# EEZ_DIB_DCP405_r1B1.net
KiCad netlist of a schematic drawn in EAGLE
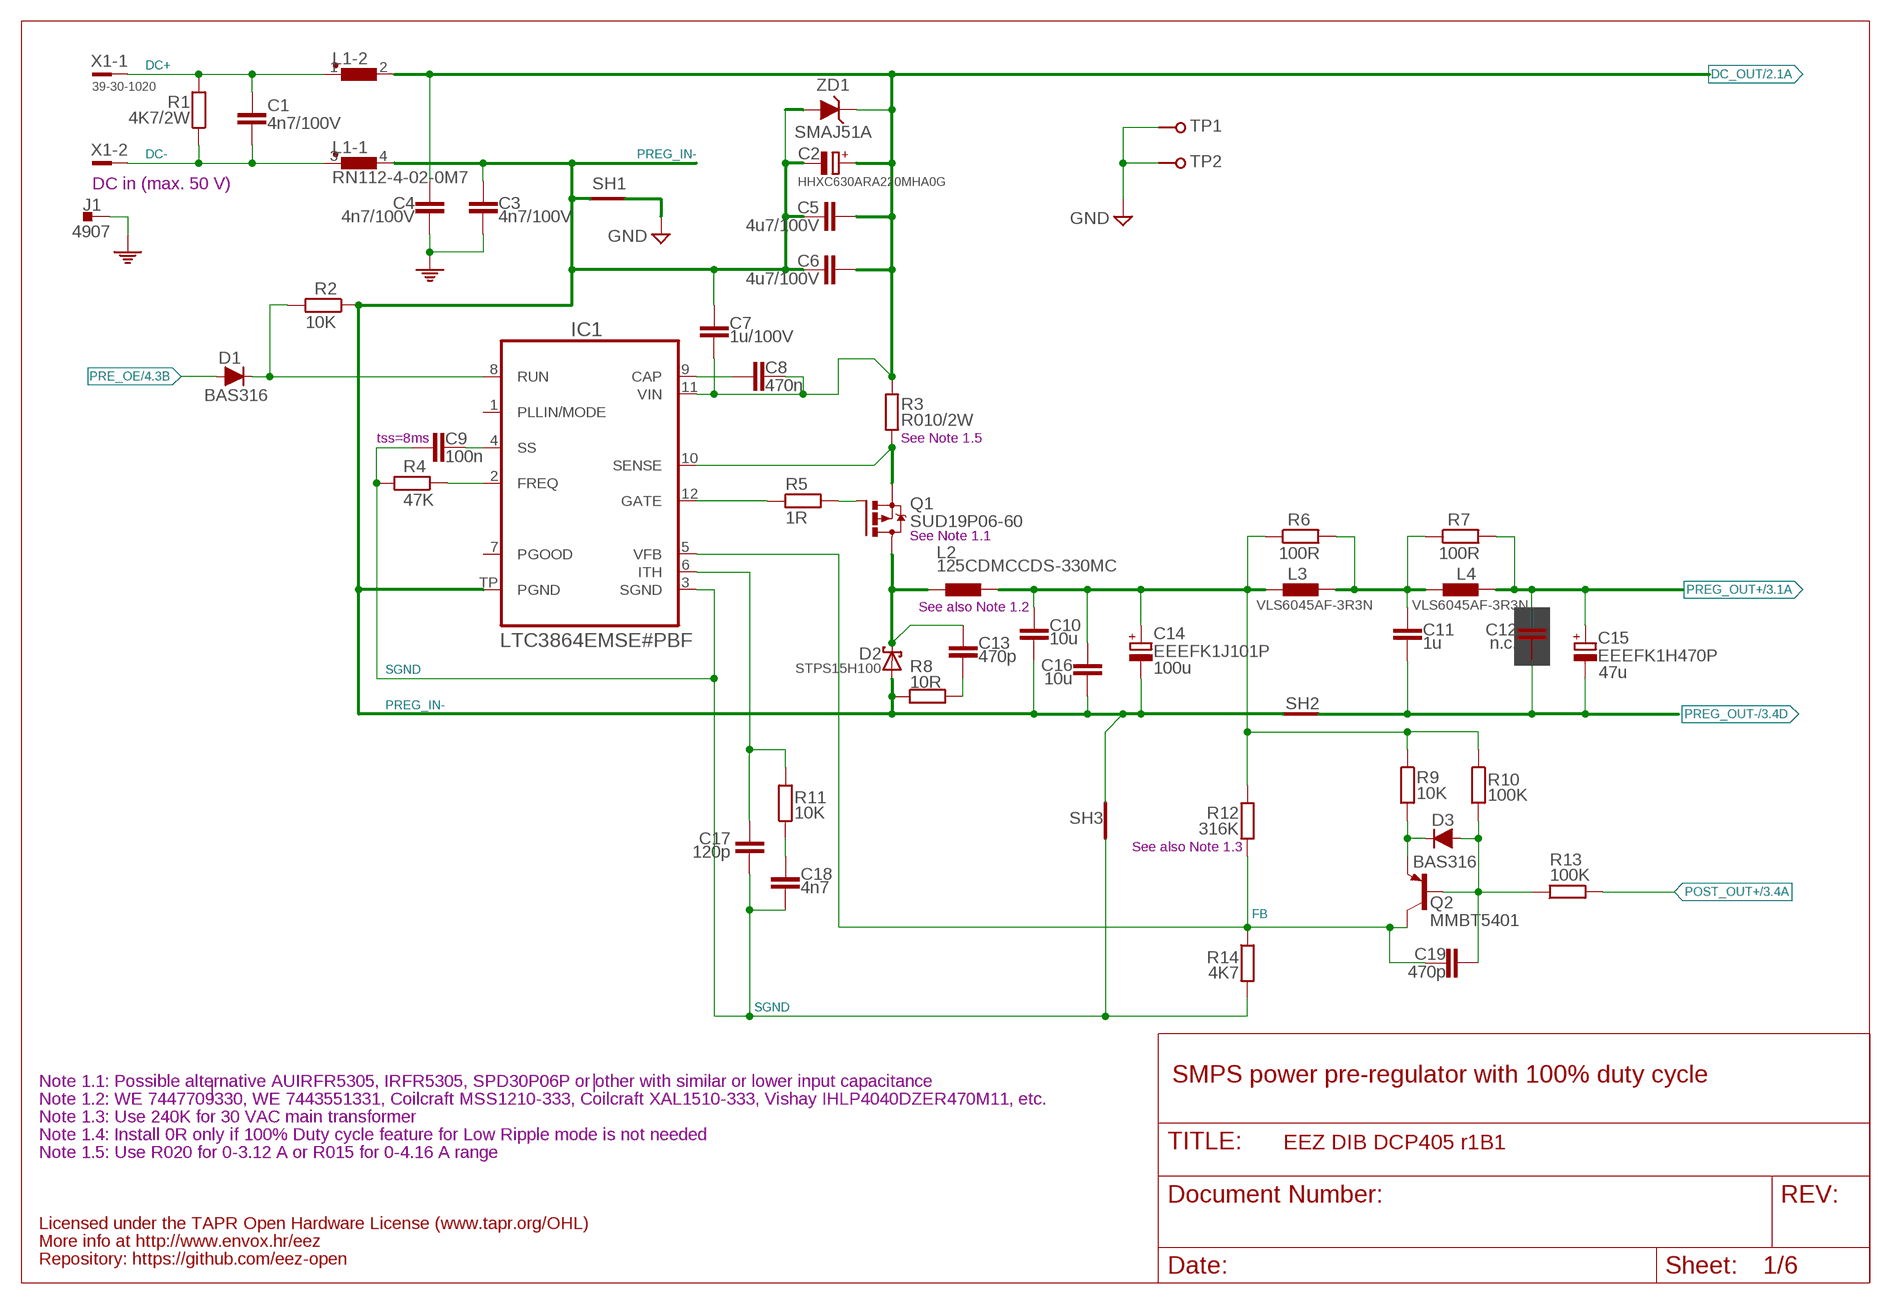
[diagram p0: schematic, sheet 1]
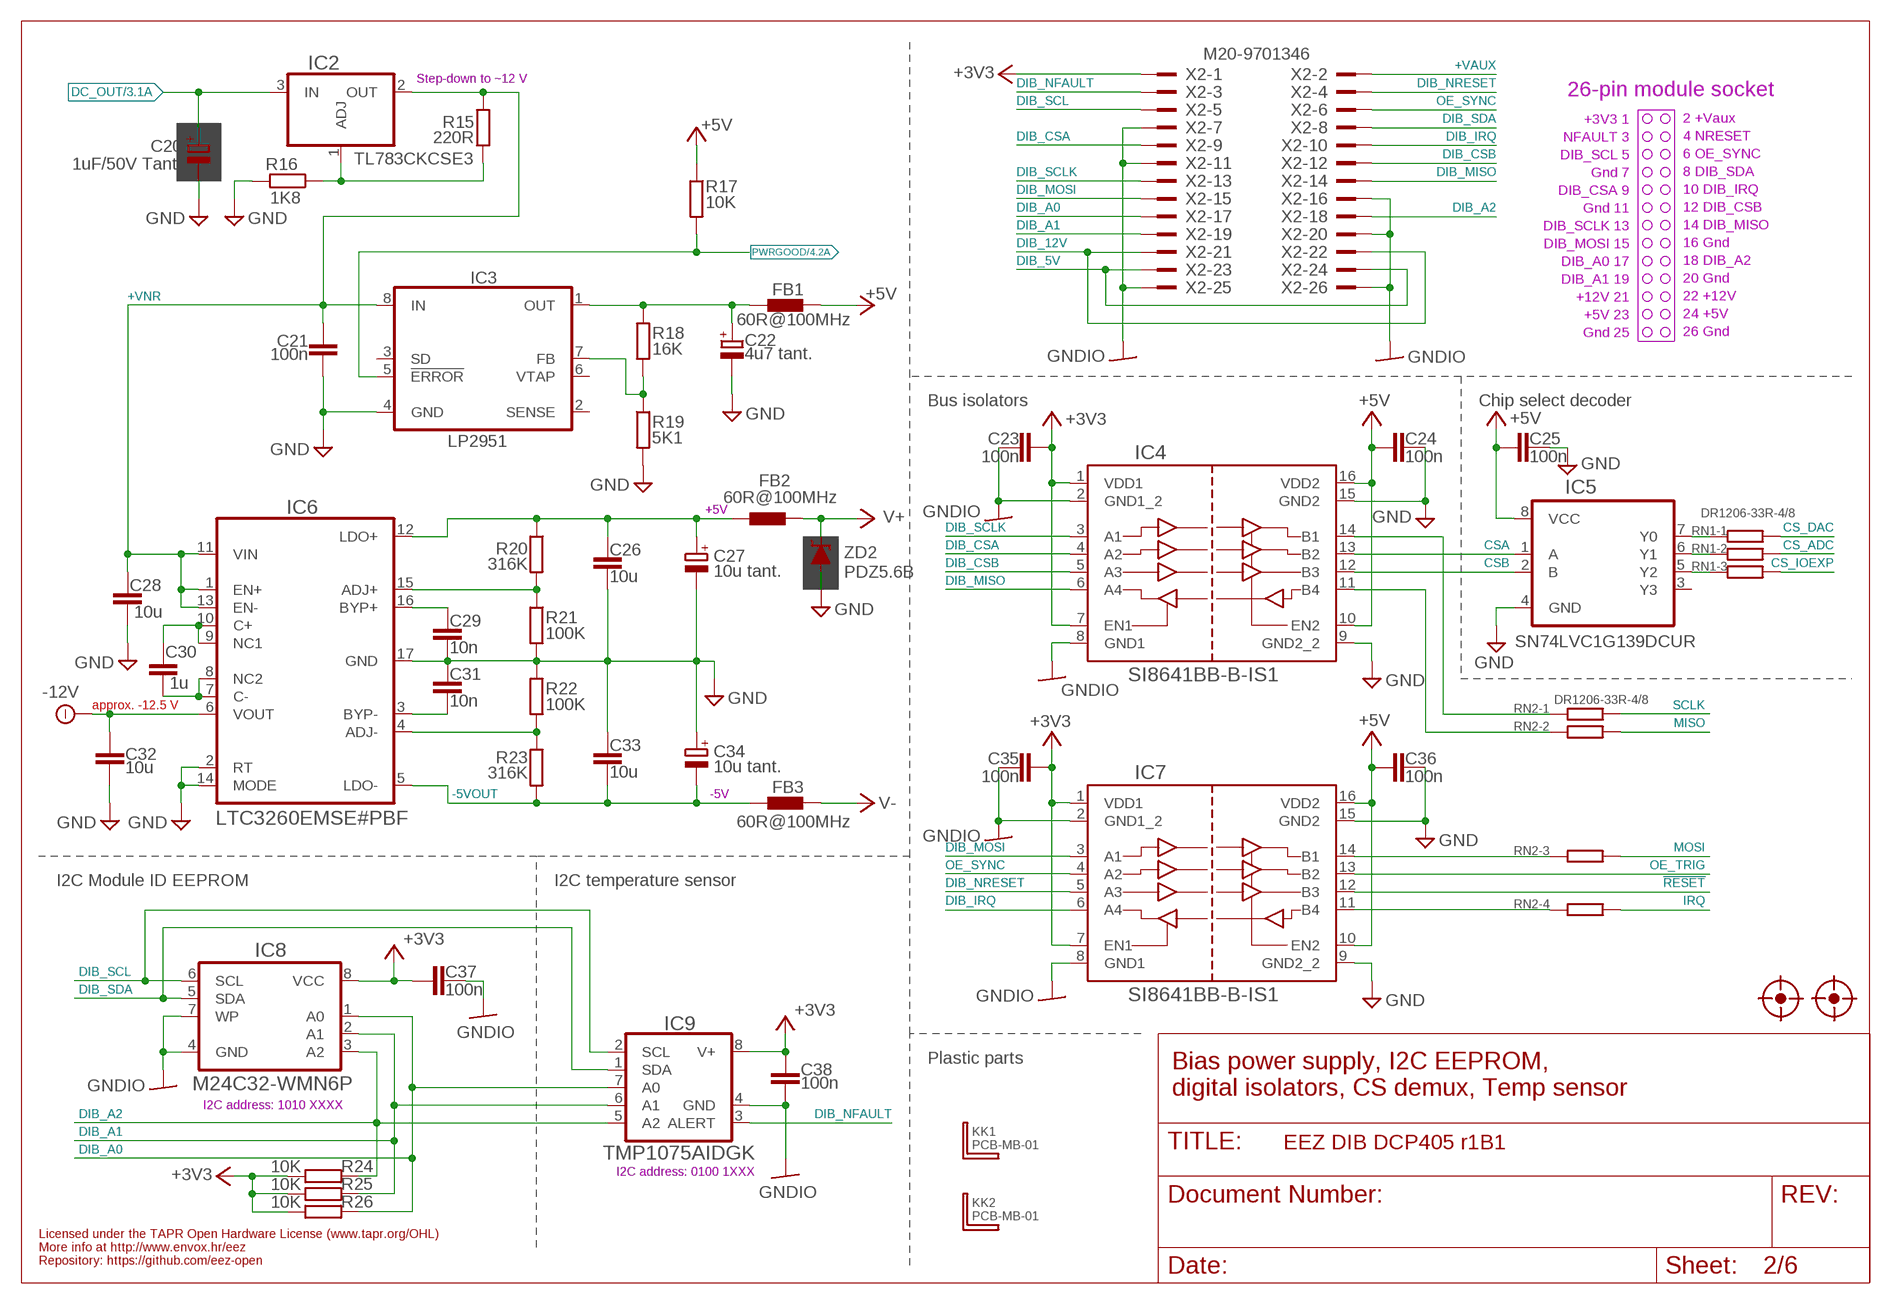
[diagram p1: schematic, sheet 2]
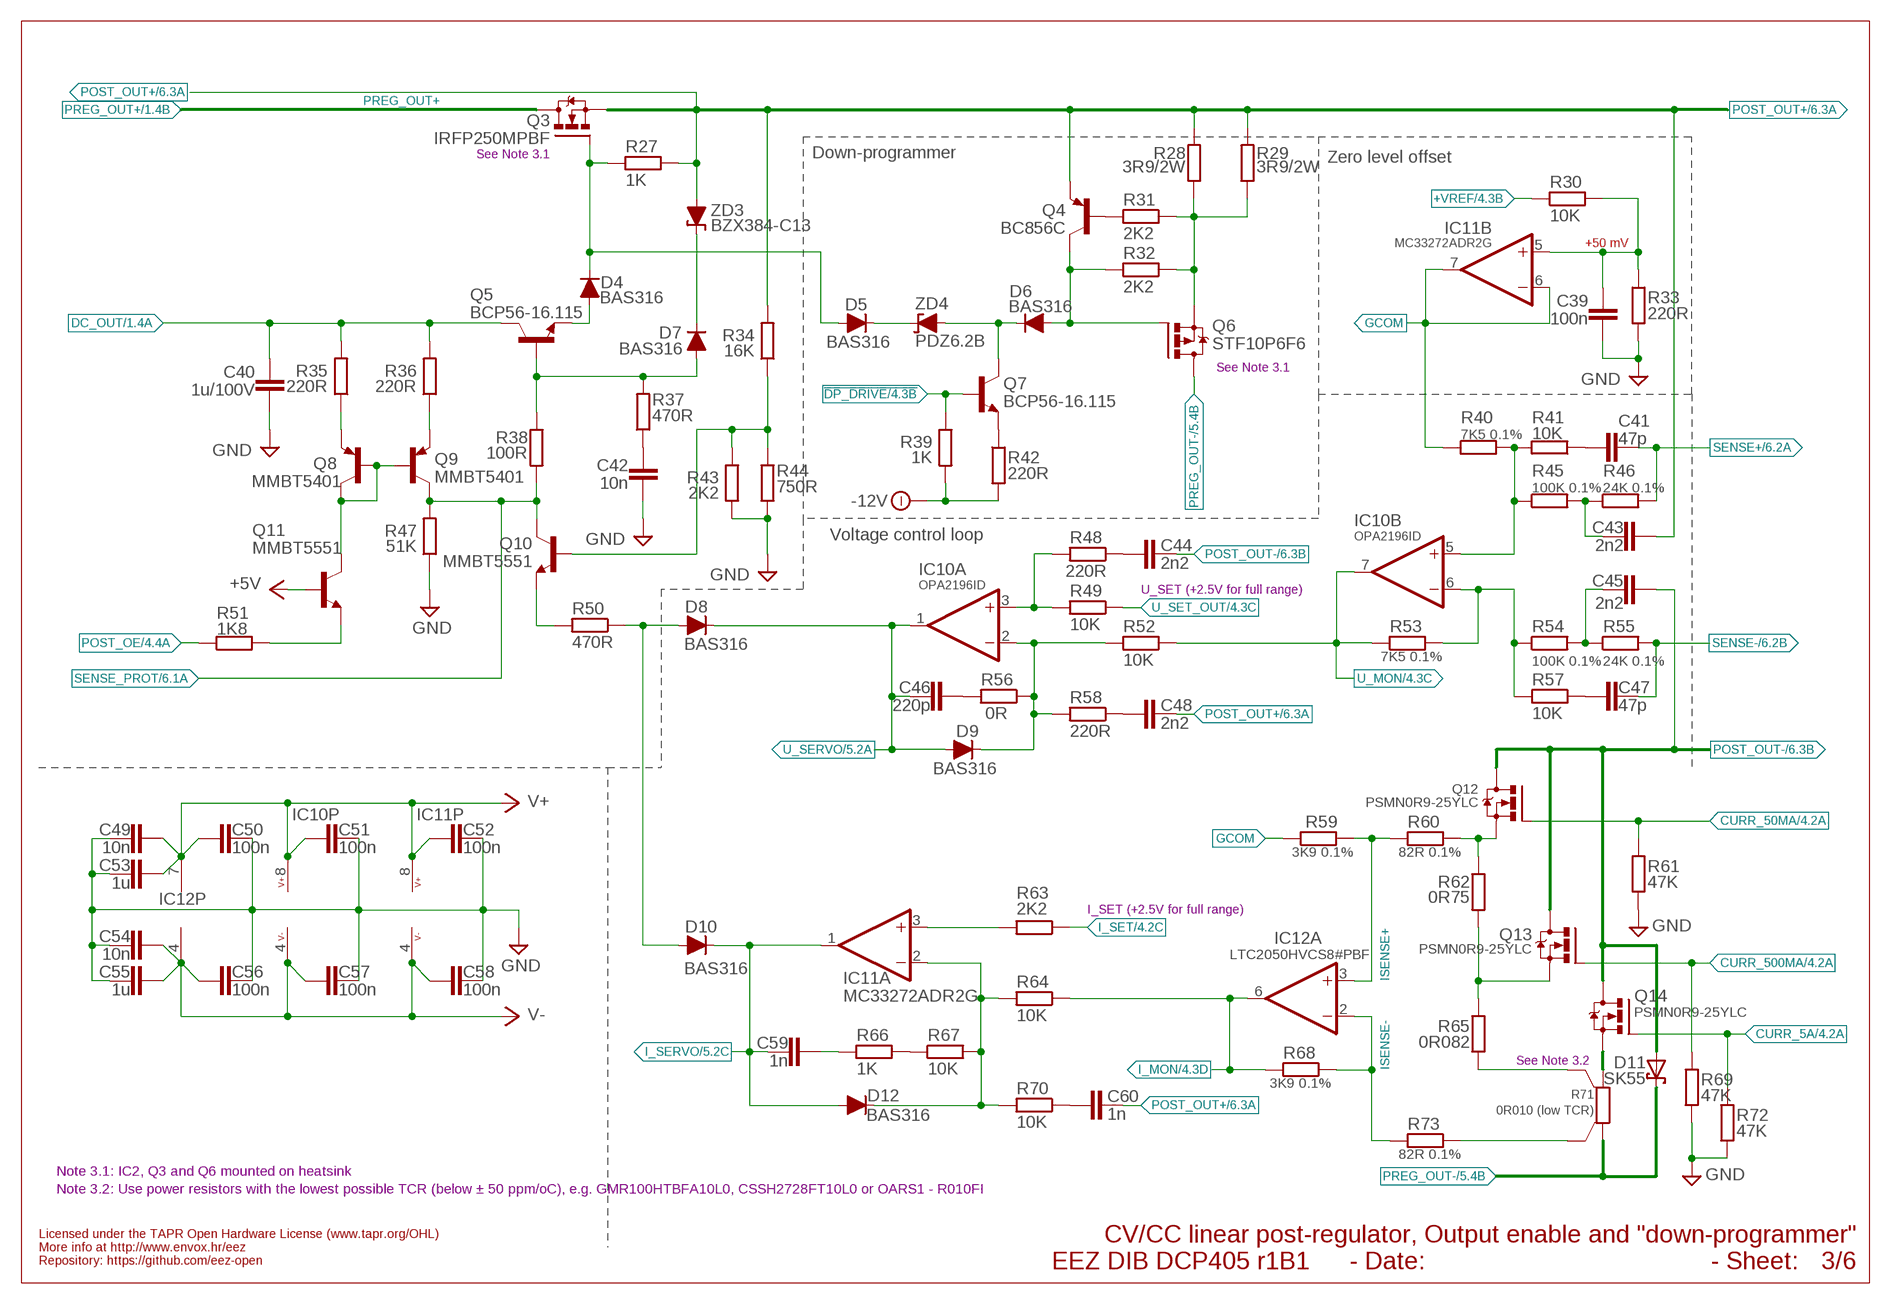
[diagram p2: schematic, sheet 3]
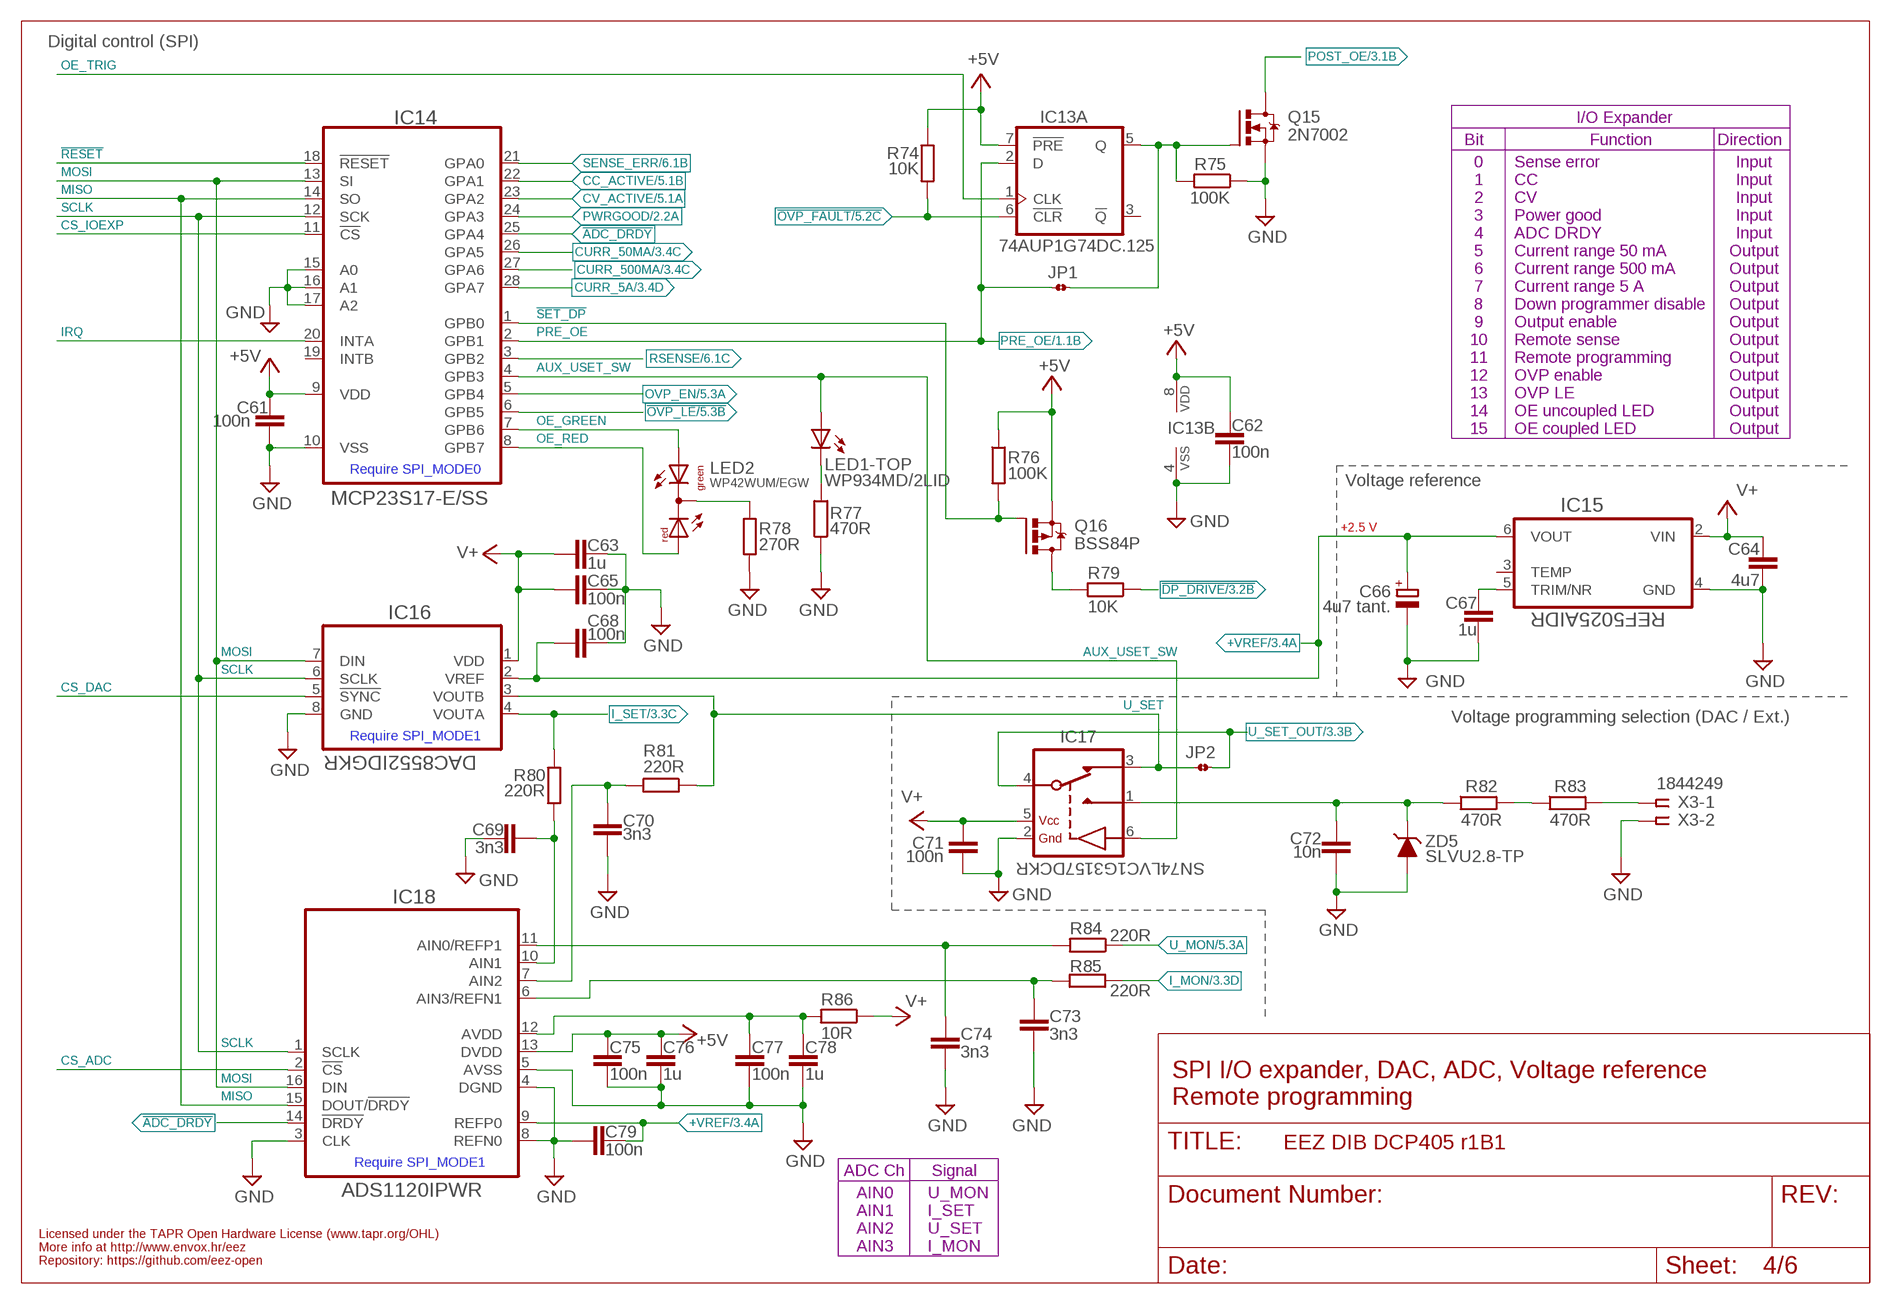
[diagram p3: schematic, sheet 4]
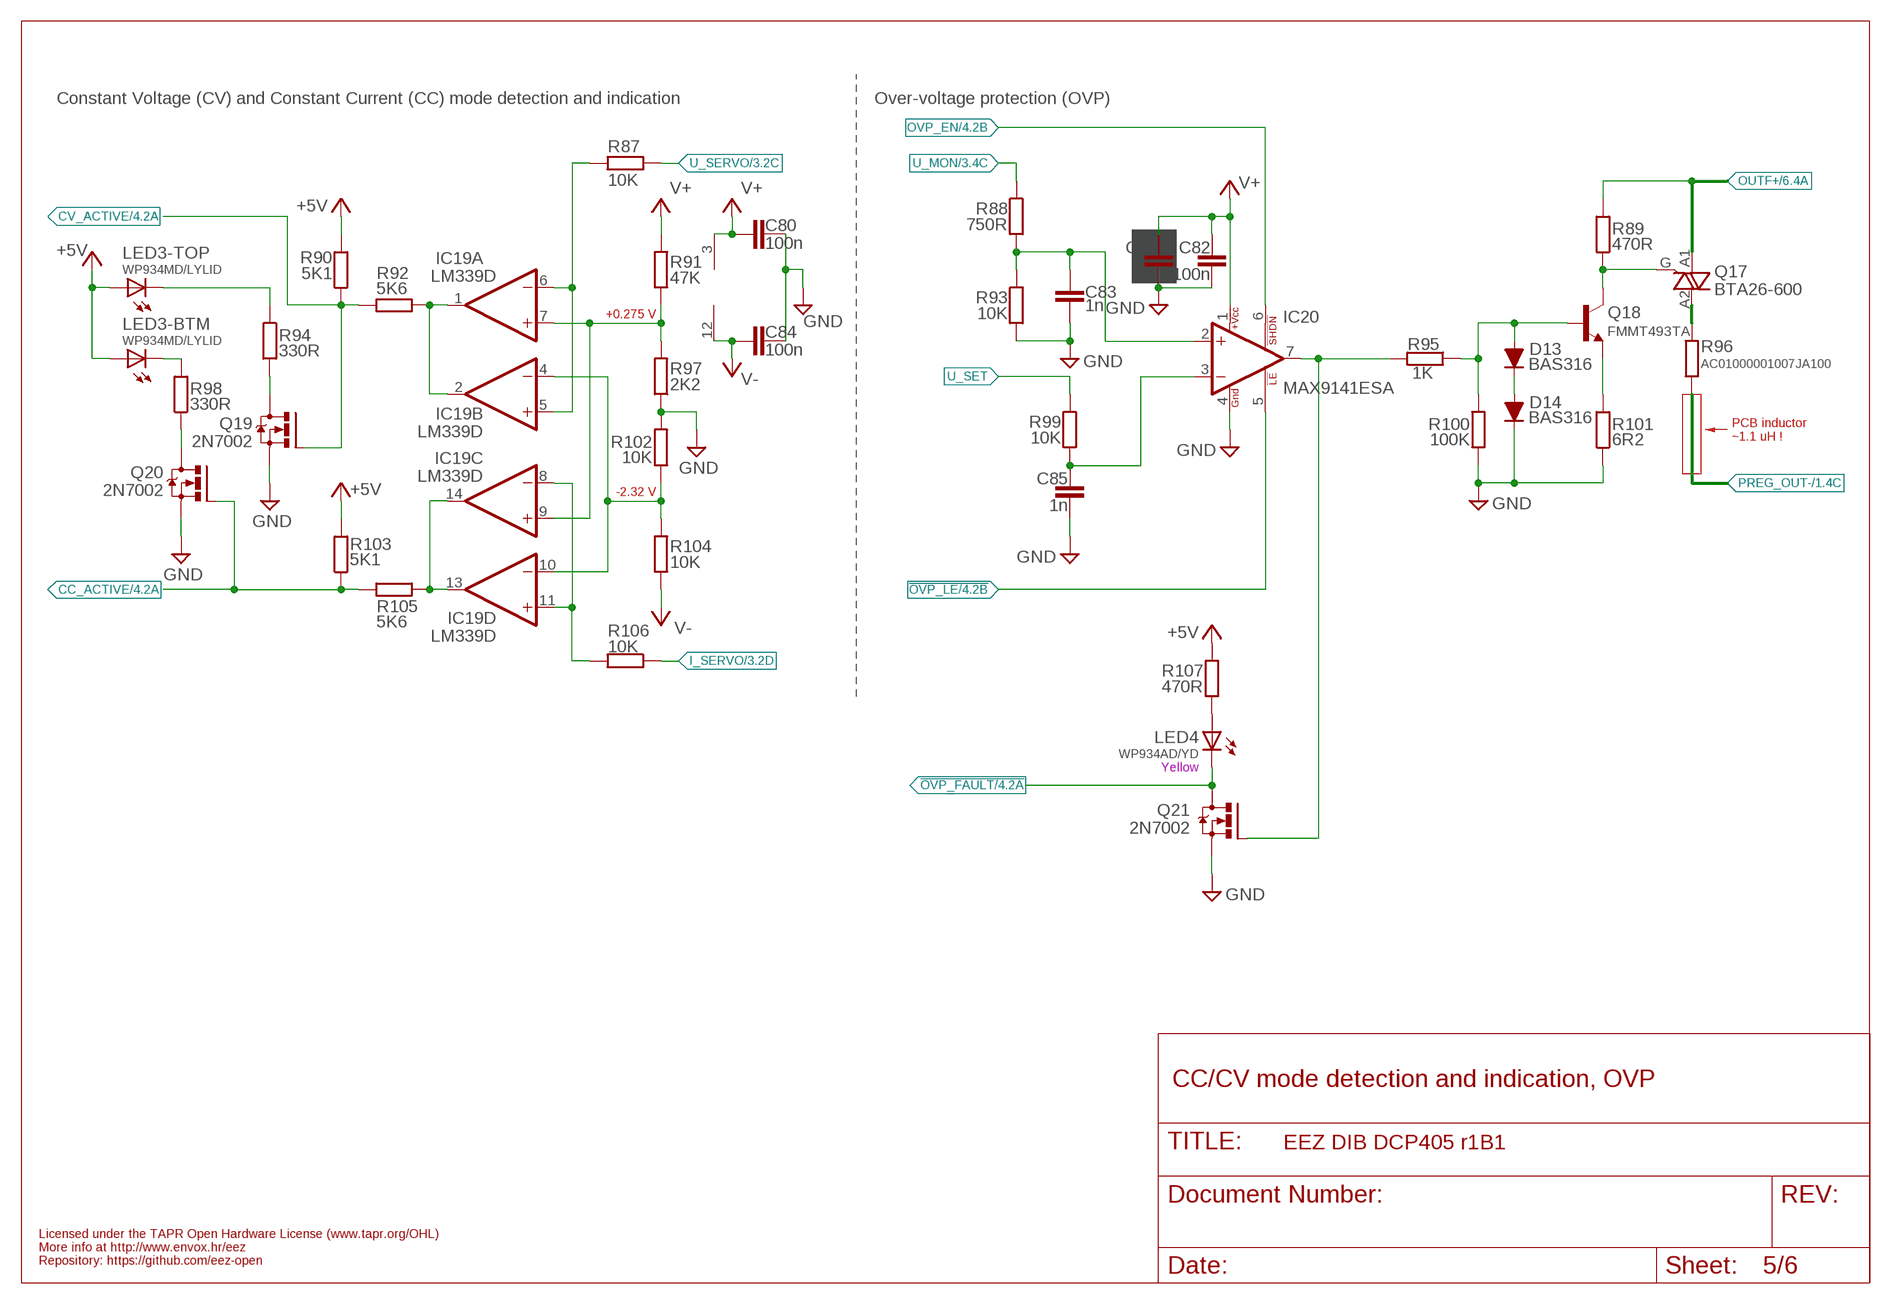
[diagram p4: schematic, sheet 5]
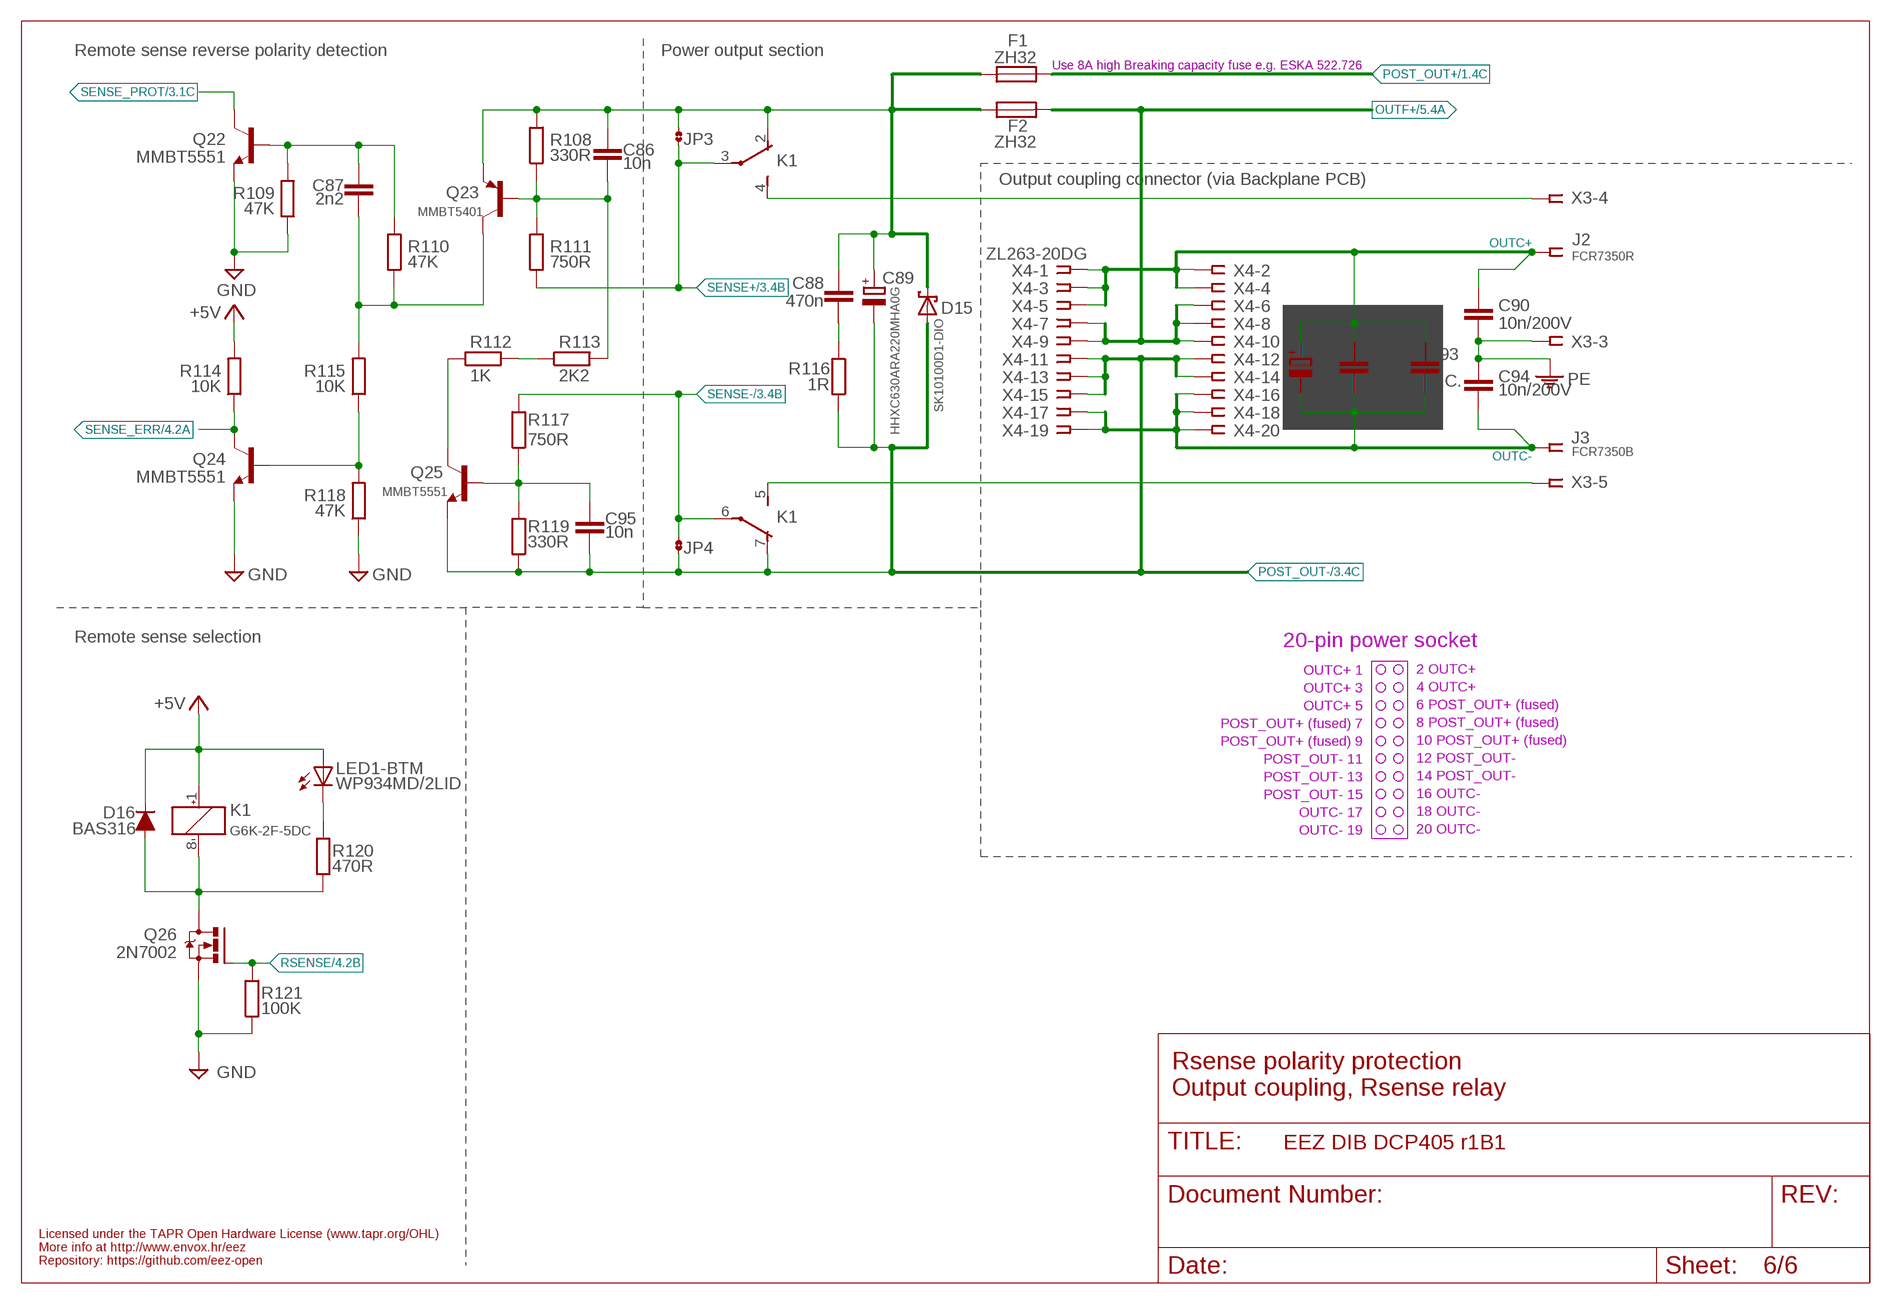
[diagram p5: schematic, sheet 6]

(export (version "E")
  (design (tool "Eeschema 10.0.6"))
  (components
    (comp (ref "C86")
      (value "10n")
      (footprint "eagle-import:C0805")
      (libsource (lib "eagle-import") (part "C-EUC0805"))
    )
    (comp (ref "C87")
      (value "2n2")
      (footprint "eagle-import:C0805")
      (libsource (lib "eagle-import") (part "C-EUC0805"))
    )
    (comp (ref "C88")
      (value "470n")
      (footprint "eagle-import:C1206")
      (libsource (lib "eagle-import") (part "C-EUC1206"))
    )
    (comp (ref "C89")
      (value "HHXC630ARA220MHA0G")
      (footprint "eagle-import:CAPAE830X1050N")
      (libsource (lib "eagle-import") (part "ECAPSMD8.3MM/HA0"))
    )
    (comp (ref "C90")
      (value "10n/200V")
      (footprint "eagle-import:C1206")
      (libsource (lib "eagle-import") (part "C-EUC1206"))
    )
    (comp (ref "C91")
      (value "N.C.")
      (footprint "eagle-import:ECAP2_5")
      (libsource (lib "eagle-import") (part "ECAP2G/5"))
    )
    (comp (ref "C92")
      (value "N.C.")
      (footprint "eagle-import:C0805")
      (libsource (lib "eagle-import") (part "C-EUC0805"))
    )
    (comp (ref "C93")
      (value "N.C.")
      (footprint "eagle-import:C0805")
      (libsource (lib "eagle-import") (part "C-EUC0805"))
    )
    (comp (ref "C94")
      (value "10n/200V")
      (footprint "eagle-import:C1206")
      (libsource (lib "eagle-import") (part "C-EUC1206"))
    )
    (comp (ref "C95")
      (value "10n")
      (footprint "eagle-import:C0805")
      (libsource (lib "eagle-import") (part "C-EUC0805"))
    )
    (comp (ref "D15")
      (value "SK10100D1-DIO")
      (footprint "eagle-import:TO252-L")
      (libsource (lib "eagle-import") (part "SCHOTTKY-DUAL_A_L"))
    )
    (comp (ref "D16")
      (value "BAS316")
      (footprint "eagle-import:SOD323-R")
      (libsource (lib "eagle-import") (part "DIODESOD323R"))
    )
    (comp (ref "F1")
      (value "ZH32")
      (footprint "eagle-import:ZH32")
      (libsource (lib "eagle-import") (part "ZH32"))
    )
    (comp (ref "F2")
      (value "ZH32")
      (footprint "eagle-import:ZH32")
      (libsource (lib "eagle-import") (part "ZH32"))
    )
    (comp (ref "J2")
      (value "FCR7350R")
      (footprint "eagle-import:S16N-PC")
      (libsource (lib "eagle-import") (part "BINDING_POSTCLIFF"))
    )
    (comp (ref "J3")
      (value "FCR7350B")
      (footprint "eagle-import:S16N-PC")
      (libsource (lib "eagle-import") (part "BINDING_POSTCLIFF"))
    )
    (comp (ref "JP3")
      (value "JP2-CUT")
      (footprint "eagle-import:JP2-CUT")
      (libsource (lib "eagle-import") (part "JP2-CUT"))
    )
    (comp (ref "JP4")
      (value "JP2-CUT")
      (footprint "eagle-import:JP2-CUT")
      (libsource (lib "eagle-import") (part "JP2-CUT"))
    )
    (comp (ref "K1")
      (value "G6K-2F-5DC")
      (footprint "eagle-import:G6K-2F")
      (fields
        (field (name "MF") "OMRON COMPONENTS USA")
        (field (name "MPN") "G6K-2F DC24")
        (field (name "MF_1") "OMRON COMPONENTS USA")
        (field (name "MPN_1") "G6K-2F DC24")
        (field (name "OC_FARNELL") "1690427")
        (field (name "OC_NEWARK") "36K7467")
      )
      (libsource (lib "eagle-import") (part "G6K-2F"))
    )
    (comp (ref "LED1")
      (value "WP934MD/2LID")
      (footprint "eagle-import:WP934MD")
      (libsource (lib "eagle-import") (part "WP934MD/2LID"))
    )
    (comp (ref "Q22")
      (value "MMBT5551")
      (footprint "eagle-import:SOT23-BEC")
      (libsource (lib "eagle-import") (part "-NPN-SOT23-BECMMBT5551LT1"))
    )
    (comp (ref "Q23")
      (value "MMBT5401")
      (footprint "eagle-import:SOT23-BEC")
      (libsource (lib "eagle-import") (part "-PNP-SOT23-BECBC857B"))
    )
    (comp (ref "Q24")
      (value "MMBT5551")
      (footprint "eagle-import:SOT23-BEC")
      (libsource (lib "eagle-import") (part "-NPN-SOT23-BECMMBT5551LT1"))
    )
    (comp (ref "Q25")
      (value "MMBT5551")
      (footprint "eagle-import:SOT23-BEC")
      (libsource (lib "eagle-import") (part "-NPN-SOT23-BECMMBT5551LT1"))
    )
    (comp (ref "Q26")
      (value "2N7002")
      (footprint "eagle-import:SOT103P240X110-3N")
      (fields
        (field (name "MPN") "2N7002-7-F")
        (field (name "MPN_1") "2N7002-7-F")
        (field (name "OC_FARNELL") "1713823")
        (field (name "OC_NEWARK") "25R5679")
        (field (name "PACKAGE") "SOT-23-3")
        (field (name "SUPPLIER") "DIODES INC.")
      )
      (libsource (lib "eagle-import") (part "2N7002"))
    )
    (comp (ref "R108")
      (value "330R")
      (footprint "eagle-import:R0805")
      (libsource (lib "eagle-import") (part "R-EU_R0805"))
    )
    (comp (ref "R109")
      (value "47K")
      (footprint "eagle-import:R0805")
      (libsource (lib "eagle-import") (part "R-EU_R0805"))
    )
    (comp (ref "R110")
      (value "47K")
      (footprint "eagle-import:R0805")
      (libsource (lib "eagle-import") (part "R-EU_R0805"))
    )
    (comp (ref "R111")
      (value "750R")
      (footprint "eagle-import:R0805")
      (libsource (lib "eagle-import") (part "R-EU_R0805"))
    )
    (comp (ref "R112")
      (value "1K")
      (footprint "eagle-import:R0805")
      (libsource (lib "eagle-import") (part "R-EU_R0805"))
    )
    (comp (ref "R113")
      (value "2K2")
      (footprint "eagle-import:R0805")
      (libsource (lib "eagle-import") (part "R-EU_R0805"))
    )
    (comp (ref "R114")
      (value "10K")
      (footprint "eagle-import:R0805")
      (libsource (lib "eagle-import") (part "R-EU_R0805"))
    )
    (comp (ref "R115")
      (value "10K")
      (footprint "eagle-import:R0805")
      (libsource (lib "eagle-import") (part "R-EU_R0805"))
    )
    (comp (ref "R116")
      (value "1R")
      (footprint "eagle-import:R0805")
      (libsource (lib "eagle-import") (part "R-EU_R0805"))
    )
    (comp (ref "R117")
      (value "750R")
      (footprint "eagle-import:R0805")
      (libsource (lib "eagle-import") (part "R-EU_R0805"))
    )
    (comp (ref "R118")
      (value "47K")
      (footprint "eagle-import:R0805")
      (libsource (lib "eagle-import") (part "R-EU_R0805"))
    )
    (comp (ref "R119")
      (value "330R")
      (footprint "eagle-import:R0805")
      (libsource (lib "eagle-import") (part "R-EU_R0805"))
    )
    (comp (ref "R120")
      (value "470R")
      (footprint "eagle-import:R0805")
      (libsource (lib "eagle-import") (part "R-EU_R0805"))
    )
    (comp (ref "R121")
      (value "100K")
      (footprint "eagle-import:R0805")
      (libsource (lib "eagle-import") (part "R-EU_R0805"))
    )
    (comp (ref "X3")
      (value "1844249")
      (footprint "eagle-import:MC1,5_5-G-3,5")
      (libsource (lib "eagle-import") (part "MC1,5/5-G-3,5"))
    )
    (comp (ref "X4")
      (value "ZL263-20DG")
      (footprint "eagle-import:SSW-110-02-T-D-RA")
      (libsource (lib "eagle-import") (part "SSW-110-02-T-D-RA"))
    )
    (comp (ref "C80")
      (value "100n")
      (footprint "eagle-import:C0603")
      (libsource (lib "eagle-import") (part "C-EUC0603"))
    )
    (comp (ref "C81")
      (value "1u")
      (footprint "eagle-import:C0805")
      (libsource (lib "eagle-import") (part "C-EUC0805"))
    )
    (comp (ref "C82")
      (value "100n")
      (footprint "eagle-import:C0603")
      (libsource (lib "eagle-import") (part "C-EUC0603"))
    )
    (comp (ref "C83")
      (value "1n")
      (footprint "eagle-import:C0805")
      (libsource (lib "eagle-import") (part "C-EUC0805"))
    )
    (comp (ref "C84")
      (value "100n")
      (footprint "eagle-import:C0603")
      (libsource (lib "eagle-import") (part "C-EUC0603"))
    )
    (comp (ref "C85")
      (value "1n")
      (footprint "eagle-import:C0805")
      (libsource (lib "eagle-import") (part "C-EUC0805"))
    )
    (comp (ref "D13")
      (value "BAS316")
      (footprint "eagle-import:SOD323-R")
      (libsource (lib "eagle-import") (part "DIODESOD323R"))
    )
    (comp (ref "D14")
      (value "BAS316")
      (footprint "eagle-import:SOD323-R")
      (libsource (lib "eagle-import") (part "DIODESOD323R"))
    )
    (comp (ref "IC19")
      (value "LM339D")
      (footprint "eagle-import:SOIC127P600X175-14N")
      (libsource (lib "eagle-import") (part "LM339SO14"))
    )
    (comp (ref "IC20")
      (value "MAX9141ESA")
      (footprint "eagle-import:SOIC127P600X173-8N")
      (libsource (lib "eagle-import") (part "MAX9141ESA"))
    )
    (comp (ref "LED3")
      (value "WP934MD/LYLID")
      (footprint "eagle-import:WP934MD")
      (libsource (lib "eagle-import") (part "WP934MD/LYLID"))
    )
    (comp (ref "LED4")
      (value "WP934AD/YD")
      (footprint "eagle-import:WP934AD")
      (libsource (lib "eagle-import") (part "WP934AD/YD"))
    )
    (comp (ref "Q17")
      (value "BTA26-600")
      (footprint "eagle-import:TOP3_TRIAC_NOHOLE")
      (libsource (lib "eagle-import") (part "BTA41-2"))
    )
    (comp (ref "Q18")
      (value "FMMT493TA")
      (footprint "eagle-import:SOT23-BEC")
      (libsource (lib "eagle-import") (part "-NPN-SOT23-BECMMBT5551LT1"))
    )
    (comp (ref "Q19")
      (value "2N7002")
      (footprint "eagle-import:SOT103P240X110-3N")
      (fields (field (name "MPN") "2N7002-7-F"))
      (libsource (lib "eagle-import") (part "2N7002"))
    )
    (comp (ref "Q20")
      (value "2N7002")
      (footprint "eagle-import:SOT103P240X110-3N")
      (fields (field (name "MPN") "2N7002-7-F"))
      (libsource (lib "eagle-import") (part "2N7002"))
    )
    (comp (ref "Q21")
      (value "2N7002")
      (footprint "eagle-import:SOT103P240X110-3N")
      (fields
        (field (name "MPN") "2N7002-7-F")
        (field (name "MPN_1") "2N7002-7-F")
        (field (name "OC_FARNELL") "1713823")
        (field (name "OC_NEWARK") "25R5679")
        (field (name "PACKAGE") "SOT-23-3")
        (field (name "SUPPLIER") "DIODES INC.")
      )
      (libsource (lib "eagle-import") (part "2N7002"))
    )
    (comp (ref "R87")
      (value "10K")
      (footprint "eagle-import:R0805")
      (libsource (lib "eagle-import") (part "R-EU_R0805"))
    )
    (comp (ref "R88")
      (value "750R")
      (footprint "eagle-import:R0805")
      (libsource (lib "eagle-import") (part "R-EU_R0805"))
    )
    (comp (ref "R89")
      (value "470R")
      (footprint "eagle-import:R0805")
      (libsource (lib "eagle-import") (part "R-EU_R0805"))
    )
    (comp (ref "R90")
      (value "5K1")
      (footprint "eagle-import:R0805")
      (libsource (lib "eagle-import") (part "R-EU_R0805"))
    )
    (comp (ref "R91")
      (value "47K")
      (footprint "eagle-import:R0805")
      (libsource (lib "eagle-import") (part "R-EU_R0805"))
    )
    (comp (ref "R92")
      (value "5K6")
      (footprint "eagle-import:R0805")
      (libsource (lib "eagle-import") (part "R-EU_R0805"))
    )
    (comp (ref "R93")
      (value "10K")
      (footprint "eagle-import:R0805")
      (libsource (lib "eagle-import") (part "R-EU_R0805"))
    )
    (comp (ref "R94")
      (value "330R")
      (footprint "eagle-import:R0805")
      (libsource (lib "eagle-import") (part "R-EU_R0805"))
    )
    (comp (ref "R95")
      (value "1K")
      (footprint "eagle-import:R0805")
      (libsource (lib "eagle-import") (part "R-EU_R0805"))
    )
    (comp (ref "R96")
      (value "AC01000001007JA100")
      (footprint "eagle-import:0411_15")
      (libsource (lib "eagle-import") (part "R-EU_0411/15"))
    )
    (comp (ref "R97")
      (value "2K2")
      (footprint "eagle-import:R0805")
      (libsource (lib "eagle-import") (part "R-EU_R0805"))
    )
    (comp (ref "R98")
      (value "330R")
      (footprint "eagle-import:R0805")
      (libsource (lib "eagle-import") (part "R-EU_R0805"))
    )
    (comp (ref "R99")
      (value "10K")
      (footprint "eagle-import:R0805")
      (libsource (lib "eagle-import") (part "R-EU_R0805"))
    )
    (comp (ref "R100")
      (value "100K")
      (footprint "eagle-import:R0805")
      (libsource (lib "eagle-import") (part "R-EU_R0805"))
    )
    (comp (ref "R101")
      (value "6R2")
      (footprint "eagle-import:R0805")
      (libsource (lib "eagle-import") (part "R-EU_R0805"))
    )
    (comp (ref "R102")
      (value "10K")
      (footprint "eagle-import:R0805")
      (libsource (lib "eagle-import") (part "R-EU_R0805"))
    )
    (comp (ref "R103")
      (value "5K1")
      (footprint "eagle-import:R0805")
      (libsource (lib "eagle-import") (part "R-EU_R0805"))
    )
    (comp (ref "R104")
      (value "10K")
      (footprint "eagle-import:R0805")
      (libsource (lib "eagle-import") (part "R-EU_R0805"))
    )
    (comp (ref "R105")
      (value "5K6")
      (footprint "eagle-import:R0805")
      (libsource (lib "eagle-import") (part "R-EU_R0805"))
    )
    (comp (ref "R106")
      (value "10K")
      (footprint "eagle-import:R0805")
      (libsource (lib "eagle-import") (part "R-EU_R0805"))
    )
    (comp (ref "R107")
      (value "470R")
      (footprint "eagle-import:R0805")
      (libsource (lib "eagle-import") (part "R-EU_R0805"))
    )
    (comp (ref "C61")
      (value "100n")
      (footprint "eagle-import:C0603")
      (libsource (lib "eagle-import") (part "C-EUC0603"))
    )
    (comp (ref "C62")
      (value "100n")
      (footprint "eagle-import:C0603")
      (libsource (lib "eagle-import") (part "C-EUC0603"))
    )
    (comp (ref "C63")
      (value "1u")
      (footprint "eagle-import:C0805")
      (libsource (lib "eagle-import") (part "C-EUC0805"))
    )
    (comp (ref "C64")
      (value "4u7")
      (footprint "eagle-import:C1206")
      (libsource (lib "eagle-import") (part "C-EUC1206"))
    )
    (comp (ref "C65")
      (value "100n")
      (footprint "eagle-import:C0603")
      (libsource (lib "eagle-import") (part "C-EUC0603"))
    )
    (comp (ref "C66")
      (value "4u7 tant.")
      (footprint "eagle-import:EC1206")
      (libsource (lib "eagle-import") (part "ECAP1206"))
    )
    (comp (ref "C67")
      (value "1u")
      (footprint "eagle-import:C0805")
      (libsource (lib "eagle-import") (part "C-EUC0805"))
    )
    (comp (ref "C68")
      (value "100n")
      (footprint "eagle-import:C0603")
      (libsource (lib "eagle-import") (part "C-EUC0603"))
    )
    (comp (ref "C69")
      (value "3n3")
      (footprint "eagle-import:C0805")
      (libsource (lib "eagle-import") (part "C-EUC0805"))
    )
    (comp (ref "C70")
      (value "3n3")
      (footprint "eagle-import:C0805")
      (libsource (lib "eagle-import") (part "C-EUC0805"))
    )
    (comp (ref "C71")
      (value "100n")
      (footprint "eagle-import:C0603")
      (libsource (lib "eagle-import") (part "C-EUC0603"))
    )
    (comp (ref "C72")
      (value "10n")
      (footprint "eagle-import:C0805")
      (libsource (lib "eagle-import") (part "C-EUC0805"))
    )
    (comp (ref "C73")
      (value "3n3")
      (footprint "eagle-import:C0805")
      (libsource (lib "eagle-import") (part "C-EUC0805"))
    )
    (comp (ref "C74")
      (value "3n3")
      (footprint "eagle-import:C0805")
      (libsource (lib "eagle-import") (part "C-EUC0805"))
    )
    (comp (ref "C75")
      (value "100n")
      (footprint "eagle-import:C0603")
      (libsource (lib "eagle-import") (part "C-EUC0603"))
    )
    (comp (ref "C76")
      (value "1u")
      (footprint "eagle-import:C0805")
      (libsource (lib "eagle-import") (part "C-EUC0805"))
    )
    (comp (ref "C77")
      (value "100n")
      (footprint "eagle-import:C0603")
      (libsource (lib "eagle-import") (part "C-EUC0603"))
    )
    (comp (ref "C78")
      (value "1u")
      (footprint "eagle-import:C0805")
      (libsource (lib "eagle-import") (part "C-EUC0805"))
    )
    (comp (ref "C79")
      (value "100n")
      (footprint "eagle-import:C0603")
      (libsource (lib "eagle-import") (part "C-EUC0603"))
    )
    (comp (ref "IC13")
      (value "74AUP1G74DC.125")
      (footprint "eagle-import:DCU8")
      (libsource (lib "eagle-import") (part "SN74LVC1G74DCTR-VSSOP"))
    )
    (comp (ref "IC14")
      (value "MCP23S17-E/SS")
      (footprint "eagle-import:SOP65P780X200-28N")
      (libsource (lib "eagle-import") (part "MCP23S17-E/SSSSOP"))
    )
    (comp (ref "IC15")
      (value "REF5025AIDR")
      (footprint "eagle-import:SOIC127P600X175-8N")
      (libsource (lib "eagle-import") (part "REF50XX"))
    )
    (comp (ref "IC16")
      (value "DAC8552IDGKR")
      (footprint "eagle-import:DGK8-M")
      (libsource (lib "eagle-import") (part "DAC8552_DGK_8M"))
    )
    (comp (ref "IC17")
      (value "SN74LVC1G3157DCKR")
      (footprint "eagle-import:SOT65P210X110-6N")
      (libsource (lib "eagle-import") (part "SN74LVC1G3157-DCK"))
    )
    (comp (ref "IC18")
      (value "ADS1120IPWR")
      (footprint "eagle-import:PW(R-PDSO-G16)")
      (libsource (lib "eagle-import") (part "ADS1120TSSOP-16"))
    )
    (comp (ref "JP1")
      (value "JP2-CUT")
      (footprint "eagle-import:JP2-CUT")
      (libsource (lib "eagle-import") (part "JP2-CUT"))
    )
    (comp (ref "JP2")
      (value "JP2-CUT")
      (footprint "eagle-import:JP2-CUT")
      (libsource (lib "eagle-import") (part "JP2-CUT"))
    )
    (comp (ref "LED2")
      (value "WP42WUM/EGW")
      (footprint "eagle-import:L-42WUM-1EGWT")
      (libsource (lib "eagle-import") (part "LED_L-42WUM/1EGWT"))
    )
    (comp (ref "Q15")
      (value "2N7002")
      (footprint "eagle-import:SOT103P240X110-3N")
      (fields
        (field (name "MPN") "2N7002-7-F")
        (field (name "MPN_1") "2N7002-7-F")
        (field (name "OC_FARNELL") "1713823")
        (field (name "OC_NEWARK") "25R5679")
        (field (name "PACKAGE") "SOT-23-3")
        (field (name "SUPPLIER") "DIODES INC.")
      )
      (libsource (lib "eagle-import") (part "2N7002"))
    )
    (comp (ref "Q16")
      (value "BSS84P")
      (footprint "eagle-import:SOT95P237X112-3N")
      (fields (field (name "MPN") "IRLML2246TRPBF"))
      (libsource (lib "eagle-import") (part "IRLML2246TRPBF"))
    )
    (comp (ref "R74")
      (value "10K")
      (footprint "eagle-import:R0805")
      (libsource (lib "eagle-import") (part "R-EU_R0805"))
    )
    (comp (ref "R75")
      (value "100K")
      (footprint "eagle-import:R0805")
      (libsource (lib "eagle-import") (part "R-EU_R0805"))
    )
    (comp (ref "R76")
      (value "100K")
      (footprint "eagle-import:R0805")
      (libsource (lib "eagle-import") (part "R-EU_R0805"))
    )
    (comp (ref "R77")
      (value "470R")
      (footprint "eagle-import:R0805")
      (libsource (lib "eagle-import") (part "R-EU_R0805"))
    )
    (comp (ref "R78")
      (value "270R")
      (footprint "eagle-import:R0805")
      (libsource (lib "eagle-import") (part "R-EU_R0805"))
    )
    (comp (ref "R79")
      (value "10K")
      (footprint "eagle-import:R0805")
      (libsource (lib "eagle-import") (part "R-EU_R0805"))
    )
    (comp (ref "R80")
      (value "220R")
      (footprint "eagle-import:R0805")
      (libsource (lib "eagle-import") (part "R-EU_R0805"))
    )
    (comp (ref "R81")
      (value "220R")
      (footprint "eagle-import:R0805")
      (libsource (lib "eagle-import") (part "R-EU_R0805"))
    )
    (comp (ref "R82")
      (value "470R")
      (footprint "eagle-import:R0805")
      (libsource (lib "eagle-import") (part "R-EU_R0805"))
    )
    (comp (ref "R83")
      (value "470R")
      (footprint "eagle-import:R0805")
      (libsource (lib "eagle-import") (part "R-EU_R0805"))
    )
    (comp (ref "R84")
      (value "220R")
      (footprint "eagle-import:R0805")
      (libsource (lib "eagle-import") (part "R-EU_R0805"))
    )
    (comp (ref "R85")
      (value "220R")
      (footprint "eagle-import:R0805")
      (libsource (lib "eagle-import") (part "R-EU_R0805"))
    )
    (comp (ref "R86")
      (value "10R")
      (footprint "eagle-import:R1206")
      (libsource (lib "eagle-import") (part "R-EU_R1206"))
    )
    (comp (ref "ZD5")
      (value "SLVU2.8-TP")
      (footprint "eagle-import:SOT23")
      (libsource (lib "eagle-import") (part "SLVU2.8"))
    )
    (comp (ref "C1")
      (value "4n7/100V")
      (footprint "eagle-import:C1206")
      (libsource (lib "eagle-import") (part "C-EUC1206"))
    )
    (comp (ref "C2")
      (value "HHXC630ARA220MHA0G")
      (footprint "eagle-import:CAPAE830X1050N")
      (libsource (lib "eagle-import") (part "ECAPSMD8.3MM/HA0"))
    )
    (comp (ref "C3")
      (value "4n7/100V")
      (footprint "eagle-import:C1206")
      (libsource (lib "eagle-import") (part "C-EUC1206"))
    )
    (comp (ref "C4")
      (value "4n7/100V")
      (footprint "eagle-import:C1206")
      (libsource (lib "eagle-import") (part "C-EUC1206"))
    )
    (comp (ref "C5")
      (value "4u7/100V")
      (footprint "eagle-import:C1210")
      (libsource (lib "eagle-import") (part "C-EUC1210"))
    )
    (comp (ref "C6")
      (value "4u7/100V")
      (footprint "eagle-import:C1210")
      (libsource (lib "eagle-import") (part "C-EUC1210"))
    )
    (comp (ref "C7")
      (value "1u/100V")
      (footprint "eagle-import:C1206")
      (libsource (lib "eagle-import") (part "C-EUC1206"))
    )
    (comp (ref "C8")
      (value "470n")
      (footprint "eagle-import:C0805")
      (libsource (lib "eagle-import") (part "C-EUC0805"))
    )
    (comp (ref "C9")
      (value "100n")
      (footprint "eagle-import:C0603")
      (libsource (lib "eagle-import") (part "C-EUC0603"))
    )
    (comp (ref "C10")
      (value "10u")
      (footprint "eagle-import:C1210")
      (libsource (lib "eagle-import") (part "C-EUC1210"))
    )
    (comp (ref "C11")
      (value "1u")
      (footprint "eagle-import:C0805")
      (libsource (lib "eagle-import") (part "C-EUC0805"))
    )
    (comp (ref "C12")
      (value "n.c.")
      (footprint "eagle-import:C0805")
      (libsource (lib "eagle-import") (part "C-EUC0805"))
    )
    (comp (ref "C13")
      (value "470p")
      (footprint "eagle-import:C0805")
      (libsource (lib "eagle-import") (part "C-EUC0805"))
    )
    (comp (ref "C14")
      (value "EEEFK1J101P")
      (footprint "eagle-import:CAPAE1030X1050N")
      (libsource (lib "eagle-import") (part "ECAP10X10"))
    )
    (comp (ref "C15")
      (value "EEEFK1H470P")
      (footprint "eagle-import:CAPAE830X1050N")
      (libsource (lib "eagle-import") (part "ECAPSMD8.3MM/HA0"))
    )
    (comp (ref "C16")
      (value "10u")
      (footprint "eagle-import:C1210")
      (libsource (lib "eagle-import") (part "C-EUC1210"))
    )
    (comp (ref "C17")
      (value "120p")
      (footprint "eagle-import:C0805")
      (libsource (lib "eagle-import") (part "C-EUC0805"))
    )
    (comp (ref "C18")
      (value "4n7")
      (footprint "eagle-import:C0805")
      (libsource (lib "eagle-import") (part "C-EUC0805"))
    )
    (comp (ref "C19")
      (value "470p")
      (footprint "eagle-import:C0805")
      (libsource (lib "eagle-import") (part "C-EUC0805"))
    )
    (comp (ref "D1")
      (value "BAS316")
      (footprint "eagle-import:SOD323-R")
      (libsource (lib "eagle-import") (part "DIODESOD323R"))
    )
    (comp (ref "D2")
      (value "STPS15H100")
      (footprint "eagle-import:TO252-L")
      (libsource (lib "eagle-import") (part "SCHOTTKY-DUAL_A_L"))
    )
    (comp (ref "D3")
      (value "BAS316")
      (footprint "eagle-import:SOD323-R")
      (libsource (lib "eagle-import") (part "DIODESOD323R"))
    )
    (comp (ref "IC1")
      (value "LTC3864EMSE#PBF")
      (footprint "eagle-import:LTC_05-08-1666")
      (libsource (lib "eagle-import") (part "LTC3864"))
    )
    (comp (ref "J1")
      (value "4907")
      (footprint "eagle-import:PCB_TAB-4907")
      (libsource (lib "eagle-import") (part "PCB_TAB-4907"))
    )
    (comp (ref "L1")
      (value "RN112-4-02-0M7")
      (footprint "eagle-import:RN112")
      (libsource (lib "eagle-import") (part "RN112"))
    )
    (comp (ref "L2")
      (value "125CDMCCDS-330MC")
      (footprint "eagle-import:125CDMCC_DS")
      (libsource (lib "eagle-import") (part "125CDMCC/DS"))
    )
    (comp (ref "L3")
      (value "VLS6045AF-3R3N")
      (footprint "eagle-import:COILCRAFT_HPI0630")
      (libsource (lib "eagle-import") (part "COILCRAFT_HPI0630"))
    )
    (comp (ref "L4")
      (value "VLS6045AF-3R3N")
      (footprint "eagle-import:COILCRAFT_HPI0630")
      (libsource (lib "eagle-import") (part "COILCRAFT_HPI0630"))
    )
    (comp (ref "Q1")
      (value "SUD19P06-60")
      (footprint "eagle-import:TO229P990X239-3N")
      (libsource (lib "eagle-import") (part "P-MOSFETDPAK"))
    )
    (comp (ref "Q2")
      (value "MMBT5401")
      (footprint "eagle-import:SOT23-BEC")
      (libsource (lib "eagle-import") (part "-PNP-SOT23-BECBC857B"))
    )
    (comp (ref "R1")
      (value "4K7/2W")
      (footprint "eagle-import:R2512")
      (libsource (lib "eagle-import") (part "R-EU_R2512"))
    )
    (comp (ref "R2")
      (value "10K")
      (footprint "eagle-import:R0805")
      (libsource (lib "eagle-import") (part "R-EU_R0805"))
    )
    (comp (ref "R3")
      (value "R010/2W")
      (footprint "eagle-import:R2512")
      (libsource (lib "eagle-import") (part "R-EU_R2512"))
    )
    (comp (ref "R4")
      (value "47K")
      (footprint "eagle-import:R0805")
      (libsource (lib "eagle-import") (part "R-EU_R0805"))
    )
    (comp (ref "R5")
      (value "1R")
      (footprint "eagle-import:R0805")
      (libsource (lib "eagle-import") (part "R-EU_R0805"))
    )
    (comp (ref "R6")
      (value "100R")
      (footprint "eagle-import:R0805")
      (libsource (lib "eagle-import") (part "R-EU_R0805"))
    )
    (comp (ref "R7")
      (value "100R")
      (footprint "eagle-import:R0805")
      (libsource (lib "eagle-import") (part "R-EU_R0805"))
    )
    (comp (ref "R8")
      (value "10R")
      (footprint "eagle-import:R1206")
      (libsource (lib "eagle-import") (part "R-EU_R1206"))
    )
    (comp (ref "R9")
      (value "10K")
      (footprint "eagle-import:R0805")
      (libsource (lib "eagle-import") (part "R-EU_R0805"))
    )
    (comp (ref "R10")
      (value "100K")
      (footprint "eagle-import:R0805")
      (libsource (lib "eagle-import") (part "R-EU_R0805"))
    )
    (comp (ref "R11")
      (value "10K")
      (footprint "eagle-import:R0805")
      (libsource (lib "eagle-import") (part "R-EU_R0805"))
    )
    (comp (ref "R12")
      (value "316K")
      (footprint "eagle-import:R0805")
      (libsource (lib "eagle-import") (part "R-EU_R0805"))
    )
    (comp (ref "R13")
      (value "100K")
      (footprint "eagle-import:R0805")
      (libsource (lib "eagle-import") (part "R-EU_R0805"))
    )
    (comp (ref "R14")
      (value "4K7")
      (footprint "eagle-import:R0805")
      (libsource (lib "eagle-import") (part "R-EU_R0805"))
    )
    (comp (ref "SH1")
      (value "SHORTNOHOLE")
      (footprint "eagle-import:SHORT_NOHOLE")
      (libsource (lib "eagle-import") (part "SHORTNOHOLE"))
    )
    (comp (ref "SH2")
      (value "Pgnd to Pout- short")
      (footprint "eagle-import:SHORT_NOHOLE")
      (libsource (lib "eagle-import") (part "SHORTNOHOLE"))
    )
    (comp (ref "SH3")
      (value "Sgnd to Pgnd short")
      (footprint "eagle-import:SHORT_NOHOLE")
      (libsource (lib "eagle-import") (part "SHORTNOHOLE"))
    )
    (comp (ref "TP1")
      (value "PCB_TEST_TABSHIELD")
      (footprint "eagle-import:PCB_SHIELD_TAB")
      (libsource (lib "eagle-import") (part "PCB_TEST_TABSHIELD"))
    )
    (comp (ref "TP2")
      (value "PCB_TEST_TABSHIELD")
      (footprint "eagle-import:PCB_SHIELD_TAB")
      (libsource (lib "eagle-import") (part "PCB_TEST_TABSHIELD"))
    )
    (comp (ref "X1")
      (value "39-30-1020")
      (footprint "eagle-import:MINIFIT_39301020")
      (libsource (lib "eagle-import") (part "MINIFIT_39301020"))
    )
    (comp (ref "ZD1")
      (value "SMAJ51A")
      (footprint "eagle-import:DO214AA")
      (libsource (lib "eagle-import") (part "P6SMB68A"))
    )
    (comp (ref "C39")
      (value "100n")
      (footprint "eagle-import:C0603")
      (libsource (lib "eagle-import") (part "C-EUC0603"))
    )
    (comp (ref "C40")
      (value "1u/100V")
      (footprint "eagle-import:C1206")
      (libsource (lib "eagle-import") (part "C-EUC1206"))
    )
    (comp (ref "C41")
      (value "47p")
      (footprint "eagle-import:C0805")
      (libsource (lib "eagle-import") (part "C-EUC0805"))
    )
    (comp (ref "C42")
      (value "10n")
      (footprint "eagle-import:C0805")
      (libsource (lib "eagle-import") (part "C-EUC0805"))
    )
    (comp (ref "C43")
      (value "2n2")
      (footprint "eagle-import:C0805")
      (libsource (lib "eagle-import") (part "C-EUC0805"))
    )
    (comp (ref "C44")
      (value "2n2")
      (footprint "eagle-import:C0805")
      (libsource (lib "eagle-import") (part "C-EUC0805"))
    )
    (comp (ref "C45")
      (value "2n2")
      (footprint "eagle-import:C0805")
      (libsource (lib "eagle-import") (part "C-EUC0805"))
    )
    (comp (ref "C46")
      (value "220p")
      (footprint "eagle-import:C0805")
      (libsource (lib "eagle-import") (part "C-EUC0805"))
    )
    (comp (ref "C47")
      (value "47p")
      (footprint "eagle-import:C0805")
      (libsource (lib "eagle-import") (part "C-EUC0805"))
    )
    (comp (ref "C48")
      (value "2n2")
      (footprint "eagle-import:C0805")
      (libsource (lib "eagle-import") (part "C-EUC0805"))
    )
    (comp (ref "C49")
      (value "10n")
      (footprint "eagle-import:C0805")
      (libsource (lib "eagle-import") (part "C-EUC0805"))
    )
    (comp (ref "C50")
      (value "100n")
      (footprint "eagle-import:C0603")
      (libsource (lib "eagle-import") (part "C-EUC0603"))
    )
    (comp (ref "C51")
      (value "100n")
      (footprint "eagle-import:C0603")
      (libsource (lib "eagle-import") (part "C-EUC0603"))
    )
    (comp (ref "C52")
      (value "100n")
      (footprint "eagle-import:C0603")
      (libsource (lib "eagle-import") (part "C-EUC0603"))
    )
    (comp (ref "C53")
      (value "1u")
      (footprint "eagle-import:C0805")
      (libsource (lib "eagle-import") (part "C-EUC0805"))
    )
    (comp (ref "C54")
      (value "10n")
      (footprint "eagle-import:C0805")
      (libsource (lib "eagle-import") (part "C-EUC0805"))
    )
    (comp (ref "C55")
      (value "1u")
      (footprint "eagle-import:C0805")
      (libsource (lib "eagle-import") (part "C-EUC0805"))
    )
    (comp (ref "C56")
      (value "100n")
      (footprint "eagle-import:C0603")
      (libsource (lib "eagle-import") (part "C-EUC0603"))
    )
    (comp (ref "C57")
      (value "100n")
      (footprint "eagle-import:C0603")
      (libsource (lib "eagle-import") (part "C-EUC0603"))
    )
    (comp (ref "C58")
      (value "100n")
      (footprint "eagle-import:C0603")
      (libsource (lib "eagle-import") (part "C-EUC0603"))
    )
    (comp (ref "C59")
      (value "1n")
      (footprint "eagle-import:C0805")
      (libsource (lib "eagle-import") (part "C-EUC0805"))
    )
    (comp (ref "C60")
      (value "1n")
      (footprint "eagle-import:C0805")
      (libsource (lib "eagle-import") (part "C-EUC0805"))
    )
    (comp (ref "D4")
      (value "BAS316")
      (footprint "eagle-import:SOD323-R")
      (libsource (lib "eagle-import") (part "DIODESOD323R"))
    )
    (comp (ref "D5")
      (value "BAS316")
      (footprint "eagle-import:SOD323-R")
      (libsource (lib "eagle-import") (part "DIODESOD323R"))
    )
    (comp (ref "D6")
      (value "BAS316")
      (footprint "eagle-import:SOD323-R")
      (libsource (lib "eagle-import") (part "DIODESOD323R"))
    )
    (comp (ref "D7")
      (value "BAS316")
      (footprint "eagle-import:SOD323-R")
      (libsource (lib "eagle-import") (part "DIODESOD323R"))
    )
    (comp (ref "D8")
      (value "BAS316")
      (footprint "eagle-import:SOD323-R")
      (libsource (lib "eagle-import") (part "DIODESOD323R"))
    )
    (comp (ref "D9")
      (value "BAS316")
      (footprint "eagle-import:SOD323-R")
      (libsource (lib "eagle-import") (part "DIODESOD323R"))
    )
    (comp (ref "D10")
      (value "BAS316")
      (footprint "eagle-import:SOD323-R")
      (libsource (lib "eagle-import") (part "DIODESOD323R"))
    )
    (comp (ref "D11")
      (value "SK55")
      (footprint "eagle-import:SMB")
      (libsource (lib "eagle-import") (part "SCHOTTKYSMB"))
    )
    (comp (ref "D12")
      (value "BAS316")
      (footprint "eagle-import:SOD323-R")
      (libsource (lib "eagle-import") (part "DIODESOD323R"))
    )
    (comp (ref "IC10")
      (value "OPA2196ID")
      (footprint "eagle-import:SOIC127P600X173-8N")
      (libsource (lib "eagle-import") (part "TL072SOIC8"))
    )
    (comp (ref "IC11")
      (value "MC33272ADR2G")
      (footprint "eagle-import:SOIC127P600X173-8N")
      (libsource (lib "eagle-import") (part "TL072SOIC8"))
    )
    (comp (ref "IC12")
      (value "LTC2050HVCS8#PBF")
      (footprint "eagle-import:SOIC127P600X173-8N")
      (libsource (lib "eagle-import") (part "OP27GSZSO8"))
    )
    (comp (ref "Q3")
      (value "IRFP250MPBF")
      (footprint "eagle-import:TO247BH-CLR2")
      (libsource (lib "eagle-import") (part "IRFP240MIRROR2"))
    )
    (comp (ref "Q4")
      (value "BC856C")
      (footprint "eagle-import:SOT23-BEC")
      (libsource (lib "eagle-import") (part "-PNP-SOT23-BECBC857C"))
    )
    (comp (ref "Q5")
      (value "BCP56-16.115")
      (footprint "eagle-import:SOT230P700X180-4N")
      (libsource (lib "eagle-import") (part "BCP56"))
    )
    (comp (ref "Q6")
      (value "STF10P6F6")
      (footprint "eagle-import:TO220H-CLR2")
      (libsource (lib "eagle-import") (part "P-MOSFETMIRROR2"))
    )
    (comp (ref "Q7")
      (value "BCP56-16.115")
      (footprint "eagle-import:SOT230P700X180-4N")
      (libsource (lib "eagle-import") (part "BCP56"))
    )
    (comp (ref "Q8")
      (value "MMBT5401")
      (footprint "eagle-import:SOT23-BEC")
      (libsource (lib "eagle-import") (part "-PNP-SOT23-BECBC857B"))
    )
    (comp (ref "Q9")
      (value "MMBT5401")
      (footprint "eagle-import:SOT23-BEC")
      (libsource (lib "eagle-import") (part "-PNP-SOT23-BECBC857B"))
    )
    (comp (ref "Q10")
      (value "MMBT5551")
      (footprint "eagle-import:SOT23-BEC")
      (libsource (lib "eagle-import") (part "-NPN-SOT23-BECMMBT5551LT1"))
    )
    (comp (ref "Q11")
      (value "MMBT5551")
      (footprint "eagle-import:SOT23-BEC")
      (libsource (lib "eagle-import") (part "-NPN-SOT23-BECMMBT5551LT1"))
    )
    (comp (ref "Q12")
      (value "PSMN0R9-25YLC")
      (footprint "eagle-import:SOT669")
      (libsource (lib "eagle-import") (part "N-MOSFETLFPAK"))
    )
    (comp (ref "Q13")
      (value "PSMN0R9-25YLC")
      (footprint "eagle-import:SOT669")
      (libsource (lib "eagle-import") (part "N-MOSFETLFPAK"))
    )
    (comp (ref "Q14")
      (value "PSMN0R9-25YLC")
      (footprint "eagle-import:SOT669")
      (libsource (lib "eagle-import") (part "N-MOSFETLFPAK"))
    )
    (comp (ref "R27")
      (value "1K")
      (footprint "eagle-import:R0805")
      (libsource (lib "eagle-import") (part "R-EU_R0805"))
    )
    (comp (ref "R28")
      (value "3R9/2W")
      (footprint "eagle-import:R2512")
      (libsource (lib "eagle-import") (part "R-EU_R2512"))
    )
    (comp (ref "R29")
      (value "3R9/2W")
      (footprint "eagle-import:R2512")
      (libsource (lib "eagle-import") (part "R-EU_R2512"))
    )
    (comp (ref "R30")
      (value "10K")
      (footprint "eagle-import:R0805")
      (libsource (lib "eagle-import") (part "R-EU_R0805"))
    )
    (comp (ref "R31")
      (value "2K2")
      (footprint "eagle-import:R0805")
      (libsource (lib "eagle-import") (part "R-EU_R0805"))
    )
    (comp (ref "R32")
      (value "2K2")
      (footprint "eagle-import:R0805")
      (libsource (lib "eagle-import") (part "R-EU_R0805"))
    )
    (comp (ref "R33")
      (value "220R")
      (footprint "eagle-import:R0805")
      (libsource (lib "eagle-import") (part "R-EU_R0805"))
    )
    (comp (ref "R34")
      (value "16K")
      (footprint "eagle-import:R0805")
      (libsource (lib "eagle-import") (part "R-EU_R0805"))
    )
    (comp (ref "R35")
      (value "220R")
      (footprint "eagle-import:R0805")
      (libsource (lib "eagle-import") (part "R-EU_R0805"))
    )
    (comp (ref "R36")
      (value "220R")
      (footprint "eagle-import:R0805")
      (libsource (lib "eagle-import") (part "R-EU_R0805"))
    )
    (comp (ref "R37")
      (value "470R")
      (footprint "eagle-import:R0805")
      (libsource (lib "eagle-import") (part "R-EU_R0805"))
    )
    (comp (ref "R38")
      (value "100R")
      (footprint "eagle-import:R0805")
      (libsource (lib "eagle-import") (part "R-EU_R0805"))
    )
    (comp (ref "R39")
      (value "1K")
      (footprint "eagle-import:R0805")
      (libsource (lib "eagle-import") (part "R-EU_R0805"))
    )
    (comp (ref "R40")
      (value "7K5 0.1%")
      (footprint "eagle-import:R0805")
      (libsource (lib "eagle-import") (part "R-EU_R0805"))
    )
    (comp (ref "R41")
      (value "10K")
      (footprint "eagle-import:R0805")
      (libsource (lib "eagle-import") (part "R-EU_R0805"))
    )
    (comp (ref "R42")
      (value "220R")
      (footprint "eagle-import:R0805")
      (libsource (lib "eagle-import") (part "R-EU_R0805"))
    )
    (comp (ref "R43")
      (value "2K2")
      (footprint "eagle-import:R0805")
      (libsource (lib "eagle-import") (part "R-EU_R0805"))
    )
    (comp (ref "R44")
      (value "750R")
      (footprint "eagle-import:R0805")
      (libsource (lib "eagle-import") (part "R-EU_R0805"))
    )
    (comp (ref "R45")
      (value "100K 0.1%")
      (footprint "eagle-import:R0805")
      (libsource (lib "eagle-import") (part "R-EU_R0805"))
    )
    (comp (ref "R46")
      (value "24K 0.1%")
      (footprint "eagle-import:R0805")
      (libsource (lib "eagle-import") (part "R-EU_R0805"))
    )
    (comp (ref "R47")
      (value "51K")
      (footprint "eagle-import:R0805")
      (libsource (lib "eagle-import") (part "R-EU_R0805"))
    )
    (comp (ref "R48")
      (value "220R")
      (footprint "eagle-import:R0805")
      (libsource (lib "eagle-import") (part "R-EU_R0805"))
    )
    (comp (ref "R49")
      (value "10K")
      (footprint "eagle-import:R0805")
      (libsource (lib "eagle-import") (part "R-EU_R0805"))
    )
    (comp (ref "R50")
      (value "470R")
      (footprint "eagle-import:R0805")
      (libsource (lib "eagle-import") (part "R-EU_R0805"))
    )
    (comp (ref "R51")
      (value "1K8")
      (footprint "eagle-import:R0805")
      (libsource (lib "eagle-import") (part "R-EU_R0805"))
    )
    (comp (ref "R52")
      (value "10K")
      (footprint "eagle-import:R0805")
      (libsource (lib "eagle-import") (part "R-EU_R0805"))
    )
    (comp (ref "R53")
      (value "7K5 0.1%")
      (footprint "eagle-import:R0805")
      (libsource (lib "eagle-import") (part "R-EU_R0805"))
    )
    (comp (ref "R54")
      (value "100K 0.1%")
      (footprint "eagle-import:R0805")
      (libsource (lib "eagle-import") (part "R-EU_R0805"))
    )
    (comp (ref "R55")
      (value "24K 0.1%")
      (footprint "eagle-import:R0805")
      (libsource (lib "eagle-import") (part "R-EU_R0805"))
    )
    (comp (ref "R56")
      (value "0R")
      (footprint "eagle-import:R0805")
      (libsource (lib "eagle-import") (part "R-EU_R0805"))
    )
    (comp (ref "R57")
      (value "10K")
      (footprint "eagle-import:R0805")
      (libsource (lib "eagle-import") (part "R-EU_R0805"))
    )
    (comp (ref "R58")
      (value "220R")
      (footprint "eagle-import:R0805")
      (libsource (lib "eagle-import") (part "R-EU_R0805"))
    )
    (comp (ref "R59")
      (value "3K9 0.1%")
      (footprint "eagle-import:R0805")
      (libsource (lib "eagle-import") (part "R-EU_R0805"))
    )
    (comp (ref "R60")
      (value "82R 0.1%")
      (footprint "eagle-import:R0805")
      (libsource (lib "eagle-import") (part "R-EU_R0805"))
    )
    (comp (ref "R61")
      (value "47K")
      (footprint "eagle-import:R0805")
      (libsource (lib "eagle-import") (part "R-EU_R0805"))
    )
    (comp (ref "R62")
      (value "0R75")
      (footprint "eagle-import:R1206")
      (libsource (lib "eagle-import") (part "R-EU_R1206"))
    )
    (comp (ref "R63")
      (value "2K2")
      (footprint "eagle-import:R0805")
      (libsource (lib "eagle-import") (part "R-EU_R0805"))
    )
    (comp (ref "R64")
      (value "10K")
      (footprint "eagle-import:R0805")
      (libsource (lib "eagle-import") (part "R-EU_R0805"))
    )
    (comp (ref "R65")
      (value "0R082")
      (footprint "eagle-import:R1210")
      (libsource (lib "eagle-import") (part "R-EU_R1210"))
    )
    (comp (ref "R66")
      (value "1K")
      (footprint "eagle-import:R0805")
      (libsource (lib "eagle-import") (part "R-EU_R0805"))
    )
    (comp (ref "R67")
      (value "10K")
      (footprint "eagle-import:R0805")
      (libsource (lib "eagle-import") (part "R-EU_R0805"))
    )
    (comp (ref "R68")
      (value "3K9 0.1%")
      (footprint "eagle-import:R0805")
      (libsource (lib "eagle-import") (part "R-EU_R0805"))
    )
    (comp (ref "R69")
      (value "47K")
      (footprint "eagle-import:R0805")
      (libsource (lib "eagle-import") (part "R-EU_R0805"))
    )
    (comp (ref "R70")
      (value "10K")
      (footprint "eagle-import:R0805")
      (libsource (lib "eagle-import") (part "R-EU_R0805"))
    )
    (comp (ref "R71")
      (value "0R010 (low TCR)")
      (footprint "eagle-import:R_H2728")
      (libsource (lib "eagle-import") (part "R-EU_4WIREH2728"))
    )
    (comp (ref "R72")
      (value "47K")
      (footprint "eagle-import:R0805")
      (libsource (lib "eagle-import") (part "R-EU_R0805"))
    )
    (comp (ref "R73")
      (value "82R 0.1%")
      (footprint "eagle-import:R0805")
      (libsource (lib "eagle-import") (part "R-EU_R0805"))
    )
    (comp (ref "ZD3")
      (value "BZX384-C13")
      (footprint "eagle-import:SOD323-W")
      (libsource (lib "eagle-import") (part "ZENER-DIODESOD323"))
    )
    (comp (ref "ZD4")
      (value "PDZ6.2B")
      (footprint "eagle-import:SOD323-W")
      (libsource (lib "eagle-import") (part "ZENER-DIODESOD323"))
    )
    (comp (ref "C20")
      (value "1uF/50V Tant.")
      (footprint "eagle-import:C_6032-28R")
      (libsource (lib "eagle-import") (part "CPOL-EUC/6032-28R"))
    )
    (comp (ref "C21")
      (value "100n")
      (footprint "eagle-import:C0603")
      (libsource (lib "eagle-import") (part "C-EUC0603"))
    )
    (comp (ref "C22")
      (value "4u7 tant.")
      (footprint "eagle-import:EC1206")
      (libsource (lib "eagle-import") (part "ECAP1206"))
    )
    (comp (ref "C23")
      (value "100n")
      (footprint "eagle-import:C0603")
      (libsource (lib "eagle-import") (part "C-EUC0603"))
    )
    (comp (ref "C24")
      (value "100n")
      (footprint "eagle-import:C0603")
      (libsource (lib "eagle-import") (part "C-EUC0603"))
    )
    (comp (ref "C25")
      (value "100n")
      (footprint "eagle-import:C0603")
      (libsource (lib "eagle-import") (part "C-EUC0603"))
    )
    (comp (ref "C26")
      (value "10u")
      (footprint "eagle-import:C1210")
      (libsource (lib "eagle-import") (part "C-EUC1210"))
    )
    (comp (ref "C27")
      (value "10u tant.")
      (footprint "eagle-import:EC1206")
      (libsource (lib "eagle-import") (part "ECAP1206"))
    )
    (comp (ref "C28")
      (value "10u")
      (footprint "eagle-import:C1210")
      (libsource (lib "eagle-import") (part "C-EUC1210"))
    )
    (comp (ref "C29")
      (value "10n")
      (footprint "eagle-import:C0805")
      (libsource (lib "eagle-import") (part "C-EUC0805"))
    )
    (comp (ref "C30")
      (value "1u")
      (footprint "eagle-import:C0805")
      (libsource (lib "eagle-import") (part "C-EUC0805"))
    )
    (comp (ref "C31")
      (value "10n")
      (footprint "eagle-import:C0805")
      (libsource (lib "eagle-import") (part "C-EUC0805"))
    )
    (comp (ref "C32")
      (value "10u")
      (footprint "eagle-import:C1210")
      (libsource (lib "eagle-import") (part "C-EUC1210"))
    )
    (comp (ref "C33")
      (value "10u")
      (footprint "eagle-import:C1210")
      (libsource (lib "eagle-import") (part "C-EUC1210"))
    )
    (comp (ref "C34")
      (value "10u tant.")
      (footprint "eagle-import:EC1206")
      (libsource (lib "eagle-import") (part "ECAP1206"))
    )
    (comp (ref "C35")
      (value "100n")
      (footprint "eagle-import:C0603")
      (libsource (lib "eagle-import") (part "C-EUC0603"))
    )
    (comp (ref "C36")
      (value "100n")
      (footprint "eagle-import:C0603")
      (libsource (lib "eagle-import") (part "C-EUC0603"))
    )
    (comp (ref "C37")
      (value "100n")
      (footprint "eagle-import:C0603")
      (libsource (lib "eagle-import") (part "C-EUC0603"))
    )
    (comp (ref "C38")
      (value "100n")
      (footprint "eagle-import:C0603")
      (libsource (lib "eagle-import") (part "C-EUC0603"))
    )
    (comp (ref "FB1")
      (value "60R@100MHz")
      (footprint "eagle-import:BEAD0603")
      (libsource (lib "eagle-import") (part "FERRITE_BEAD0603"))
    )
    (comp (ref "FB2")
      (value "60R@100MHz")
      (footprint "eagle-import:BEAD0603")
      (libsource (lib "eagle-import") (part "FERRITE_BEAD0603"))
    )
    (comp (ref "FB3")
      (value "60R@100MHz")
      (footprint "eagle-import:BEAD0603")
      (libsource (lib "eagle-import") (part "FERRITE_BEAD0603"))
    )
    (comp (ref "FM1")
      (value "FIDUCIAL_2")
      (footprint "eagle-import:FIDUCIAL_DUAL")
      (libsource (lib "eagle-import") (part "FIDUCIAL_2"))
    )
    (comp (ref "FM2")
      (value "FIDUCIAL_2")
      (footprint "eagle-import:FIDUCIAL_DUAL")
      (libsource (lib "eagle-import") (part "FIDUCIAL_2"))
    )
    (comp (ref "IC2")
      (value "TL783CKCSE3")
      (footprint "eagle-import:TO220H-CLR2")
      (libsource (lib "eagle-import") (part "TL783CKCSE3"))
    )
    (comp (ref "IC3")
      (value "LP2951")
      (footprint "eagle-import:SOIC127P600X175-8N")
      (libsource (lib "eagle-import") (part "LP2951SO8"))
    )
    (comp (ref "IC4")
      (value "SI8641BB-B-IS1")
      (footprint "eagle-import:SOIC-16")
      (libsource (lib "eagle-import") (part "SI8641NSOIC-16"))
    )
    (comp (ref "IC5")
      (value "SN74LVC1G139DCUR")
      (footprint "eagle-import:DCU8")
      (libsource (lib "eagle-import") (part "SN74LVC1G139-VSSOP"))
    )
    (comp (ref "IC6")
      (value "LTC3260EMSE#PBF")
      (footprint "eagle-import:SOP50P490X110-17N")
      (libsource (lib "eagle-import") (part "LTC3260MSOP16"))
    )
    (comp (ref "IC7")
      (value "SI8641BB-B-IS1")
      (footprint "eagle-import:SOIC-16")
      (libsource (lib "eagle-import") (part "SI8641NSOIC-16"))
    )
    (comp (ref "IC8")
      (value "M24C32-WMN6P")
      (footprint "eagle-import:SOIC127P600X173-8N")
      (libsource (lib "eagle-import") (part "AT24CXXSOIC8"))
    )
    (comp (ref "IC9")
      (value "TMP1075AIDGK")
      (footprint "eagle-import:DGK8")
      (libsource (lib "eagle-import") (part "TMPX75DGK"))
    )
    (comp (ref "KK1")
      (value "PCB-MB-01")
      (footprint "eagle-import:PCB-MB")
      (libsource (lib "eagle-import") (part "PCB-MB"))
    )
    (comp (ref "KK2")
      (value "PCB-MB-01")
      (footprint "eagle-import:PCB-MB")
      (libsource (lib "eagle-import") (part "PCB-MB"))
    )
    (comp (ref "R15")
      (value "220R")
      (footprint "eagle-import:R0805")
      (libsource (lib "eagle-import") (part "R-EU_R0805"))
    )
    (comp (ref "R16")
      (value "1K8")
      (footprint "eagle-import:R0805")
      (libsource (lib "eagle-import") (part "R-EU_R0805"))
    )
    (comp (ref "R17")
      (value "10K")
      (footprint "eagle-import:R0805")
      (libsource (lib "eagle-import") (part "R-EU_R0805"))
    )
    (comp (ref "R18")
      (value "16K")
      (footprint "eagle-import:R0805")
      (libsource (lib "eagle-import") (part "R-EU_R0805"))
    )
    (comp (ref "R19")
      (value "5K1")
      (footprint "eagle-import:R0805")
      (libsource (lib "eagle-import") (part "R-EU_R0805"))
    )
    (comp (ref "R20")
      (value "316K")
      (footprint "eagle-import:R0805")
      (libsource (lib "eagle-import") (part "R-EU_R0805"))
    )
    (comp (ref "R21")
      (value "100K")
      (footprint "eagle-import:R0805")
      (libsource (lib "eagle-import") (part "R-EU_R0805"))
    )
    (comp (ref "R22")
      (value "100K")
      (footprint "eagle-import:R0805")
      (libsource (lib "eagle-import") (part "R-EU_R0805"))
    )
    (comp (ref "R23")
      (value "316K")
      (footprint "eagle-import:R0805")
      (libsource (lib "eagle-import") (part "R-EU_R0805"))
    )
    (comp (ref "R24")
      (value "10K")
      (footprint "eagle-import:R0805")
      (libsource (lib "eagle-import") (part "R-EU_R0805"))
    )
    (comp (ref "R25")
      (value "10K")
      (footprint "eagle-import:R0805")
      (libsource (lib "eagle-import") (part "R-EU_R0805"))
    )
    (comp (ref "R26")
      (value "10K")
      (footprint "eagle-import:R0805")
      (libsource (lib "eagle-import") (part "R-EU_R0805"))
    )
    (comp (ref "RN1")
      (value "DR1206-33R-4/8")
      (footprint "eagle-import:CAY16")
      (libsource (lib "eagle-import") (part "R_ARRAY4"))
    )
    (comp (ref "RN2")
      (value "DR1206-33R-4/8")
      (footprint "eagle-import:CAY16")
      (libsource (lib "eagle-import") (part "R_ARRAY4"))
    )
    (comp (ref "X2")
      (value "M20-9701346")
      (footprint "eagle-import:M20-9701346")
      (libsource (lib "eagle-import") (part "M20-9701346"))
    )
    (comp (ref "ZD2")
      (value "PDZ5.6B")
      (footprint "eagle-import:SOD323-W")
      (libsource (lib "eagle-import") (part "ZENER-DIODESOD323"))
    )
  )
  (nets
    (net (code "1") (name "+3V3") (class "Default")
      (node (ref "C23") (pin "1") (pinfunction "1_1") (pintype "passive"))
      (node (ref "C35") (pin "1") (pinfunction "1_1") (pintype "passive"))
      (node (ref "C37") (pin "2") (pinfunction "2_2") (pintype "passive"))
      (node (ref "C38") (pin "1") (pinfunction "1_1") (pintype "passive"))
      (node (ref "IC4") (pin "1") (pinfunction "VDD1_1") (pintype "passive"))
      (node (ref "IC4") (pin "7") (pinfunction "EN1_7") (pintype "input"))
      (node (ref "IC7") (pin "1") (pinfunction "VDD1_1") (pintype "passive"))
      (node (ref "IC7") (pin "7") (pinfunction "EN1_7") (pintype "input"))
      (node (ref "IC8") (pin "8") (pinfunction "VCC_8") (pintype "power_in"))
      (node (ref "IC9") (pin "8") (pinfunction "V+_8") (pintype "passive"))
      (node (ref "R24") (pin "1") (pinfunction "1_1") (pintype "passive"))
      (node (ref "R25") (pin "1") (pinfunction "1_1") (pintype "passive"))
      (node (ref "R26") (pin "1") (pinfunction "1_1") (pintype "passive"))
      (node (ref "X2") (pin "1") (pinfunction "1_1") (pintype "passive"))
    )
    (net (code "2") (name "+5V") (class "Default")
      (node (ref "C24") (pin "2") (pinfunction "2_2") (pintype "passive"))
      (node (ref "C25") (pin "1") (pinfunction "1_1") (pintype "passive"))
      (node (ref "C36") (pin "2") (pinfunction "2_2") (pintype "passive"))
      (node (ref "C61") (pin "1") (pinfunction "1_1") (pintype "passive"))
      (node (ref "C62") (pin "2") (pinfunction "2_2") (pintype "passive"))
      (node (ref "C75") (pin "2") (pinfunction "2_2") (pintype "passive"))
      (node (ref "C76") (pin "2") (pinfunction "2_2") (pintype "passive"))
      (node (ref "D16") (pin "C") (pinfunction "C_C") (pintype "passive"))
      (node (ref "FB1") (pin "P$2") (pinfunction "2_P$2") (pintype "passive"))
      (node (ref "IC13") (pin "7") (pinfunction "~{PRE}_7") (pintype "input"))
      (node (ref "IC13") (pin "8") (pinfunction "VDD_8") (pintype "power_in"))
      (node (ref "IC14") (pin "9") (pinfunction "VDD_9") (pintype "power_in"))
      (node (ref "IC18") (pin "13") (pinfunction "DVDD_13") (pintype "power_in"))
      (node (ref "IC4") (pin "10") (pinfunction "EN2_10") (pintype "input"))
      (node (ref "IC4") (pin "16") (pinfunction "VDD2_16") (pintype "passive"))
      (node (ref "IC5") (pin "8") (pinfunction "VCC_8") (pintype "passive"))
      (node (ref "IC7") (pin "10") (pinfunction "EN2_10") (pintype "input"))
      (node (ref "IC7") (pin "16") (pinfunction "VDD2_16") (pintype "passive"))
      (node (ref "K1") (pin "1") (pinfunction "+_1") (pintype "passive"))
      (node (ref "LED1") (pin "BA") (pinfunction "A_BA") (pintype "passive"))
      (node (ref "LED3") (pin "BA") (pinfunction "A_BA") (pintype "passive"))
      (node (ref "LED3") (pin "TA") (pinfunction "A_TA") (pintype "passive"))
      (node (ref "Q11") (pin "B") (pinfunction "B_B") (pintype "passive"))
      (node (ref "Q16") (pin "2") (pinfunction "S_2") (pintype "passive"))
      (node (ref "R103") (pin "2") (pinfunction "2_2") (pintype "passive"))
      (node (ref "R107") (pin "1") (pinfunction "1_1") (pintype "passive"))
      (node (ref "R114") (pin "2") (pinfunction "2_2") (pintype "passive"))
      (node (ref "R17") (pin "1") (pinfunction "1_1") (pintype "passive"))
      (node (ref "R74") (pin "1") (pinfunction "1_1") (pintype "passive"))
      (node (ref "R76") (pin "1") (pinfunction "1_1") (pintype "passive"))
      (node (ref "R90") (pin "2") (pinfunction "2_2") (pintype "passive"))
    )
    (net (code "3") (name "+VAUX") (class "Default")
      (node (ref "X2") (pin "2") (pinfunction "1_2") (pintype "passive"))
    )
    (net (code "4") (name "+VNR") (class "Default")
      (node (ref "C21") (pin "1") (pinfunction "1_1") (pintype "passive"))
      (node (ref "C28") (pin "1") (pinfunction "1_1") (pintype "passive"))
      (node (ref "IC2") (pin "2") (pinfunction "OUT_2") (pintype "output"))
      (node (ref "IC3") (pin "8") (pinfunction "IN_8") (pintype "power_in"))
      (node (ref "IC6") (pin "1") (pinfunction "EN+_1") (pintype "bidirectional"))
      (node (ref "IC6") (pin "11") (pinfunction "VIN_11") (pintype "bidirectional"))
      (node (ref "IC6") (pin "13") (pinfunction "EN-_13") (pintype "bidirectional"))
      (node (ref "R15") (pin "1") (pinfunction "1_1") (pintype "passive"))
    )
    (net (code "5") (name "+VREF") (class "Default")
      (node (ref "C66") (pin "+") (pinfunction "+_+") (pintype "passive"))
      (node (ref "C68") (pin "2") (pinfunction "2_2") (pintype "passive"))
      (node (ref "C79") (pin "2") (pinfunction "2_2") (pintype "passive"))
      (node (ref "IC15") (pin "6") (pinfunction "VOUT_6") (pintype "output"))
      (node (ref "IC16") (pin "2") (pinfunction "VREF_2") (pintype "input"))
      (node (ref "IC18") (pin "9") (pinfunction "REFP0_9") (pintype "input"))
      (node (ref "R30") (pin "1") (pinfunction "1_1") (pintype "passive"))
    )
    (net (code "6") (name "-5VOUT") (class "Default")
      (node (ref "C33") (pin "2") (pinfunction "2_2") (pintype "passive"))
      (node (ref "C34") (pin "-") (pinfunction "-_-") (pintype "passive"))
      (node (ref "FB3") (pin "P$1") (pinfunction "1_P$1") (pintype "passive"))
      (node (ref "IC6") (pin "5") (pinfunction "LDO-_5") (pintype "bidirectional"))
      (node (ref "R23") (pin "2") (pinfunction "2_2") (pintype "passive"))
    )
    (net (code "7") (name "-12V") (class "Default")
      (node (ref "C32") (pin "1") (pinfunction "1_1") (pintype "passive"))
      (node (ref "IC6") (pin "6") (pinfunction "VOUT_6") (pintype "bidirectional"))
      (node (ref "R39") (pin "2") (pinfunction "2_2") (pintype "passive"))
      (node (ref "R42") (pin "2") (pinfunction "2_2") (pintype "passive"))
    )
    (net (code "8") (name "AUX_USET_SW") (class "Default")
      (node (ref "IC14") (pin "4") (pinfunction "GPB3_4") (pintype "bidirectional"))
      (node (ref "IC17") (pin "6") (pinfunction "CTRL_6") (pintype "input"))
      (node (ref "LED1") (pin "TA") (pinfunction "A_TA") (pintype "passive"))
    )
    (net (code "9") (name "CC_ACTIVE") (class "Default")
      (node (ref "IC14") (pin "22") (pinfunction "GPA1_22") (pintype "bidirectional"))
      (node (ref "Q20") (pin "1") (pinfunction "G_1") (pintype "passive"))
      (node (ref "R103") (pin "1") (pinfunction "1_1") (pintype "passive"))
      (node (ref "R105") (pin "2") (pinfunction "2_2") (pintype "passive"))
    )
    (net (code "10") (name "CSA") (class "Default")
      (node (ref "IC4") (pin "13") (pinfunction "B2_13") (pintype "output"))
      (node (ref "IC5") (pin "1") (pinfunction "A_1") (pintype "input"))
    )
    (net (code "11") (name "CSB") (class "Default")
      (node (ref "IC4") (pin "12") (pinfunction "B3_12") (pintype "output"))
      (node (ref "IC5") (pin "2") (pinfunction "B_2") (pintype "input"))
    )
    (net (code "12") (name "CS_ADC") (class "Default")
      (node (ref "IC18") (pin "2") (pinfunction "~{CS}_2") (pintype "input"))
      (node (ref "RN1") (pin "7") (pinfunction "2_7") (pintype "passive"))
    )
    (net (code "13") (name "CS_DAC") (class "Default")
      (node (ref "IC16") (pin "5") (pinfunction "~{SYNC}_5") (pintype "input"))
      (node (ref "RN1") (pin "8") (pinfunction "2_8") (pintype "passive"))
    )
    (net (code "14") (name "CS_IOEXP") (class "Default")
      (node (ref "IC14") (pin "11") (pinfunction "~{CS}_11") (pintype "input"))
      (node (ref "RN1") (pin "6") (pinfunction "2_6") (pintype "passive"))
    )
    (net (code "15") (name "CURR_5A") (class "Default")
      (node (ref "IC14") (pin "28") (pinfunction "GPA7_28") (pintype "bidirectional"))
      (node (ref "Q14") (pin "4") (pinfunction "G_4") (pintype "passive"))
      (node (ref "R72") (pin "2") (pinfunction "2_2") (pintype "passive"))
    )
    (net (code "16") (name "CURR_50MA") (class "Default")
      (node (ref "IC14") (pin "26") (pinfunction "GPA5_26") (pintype "bidirectional"))
      (node (ref "Q12") (pin "4") (pinfunction "G_4") (pintype "passive"))
      (node (ref "R61") (pin "2") (pinfunction "2_2") (pintype "passive"))
    )
    (net (code "17") (name "CURR_500MA") (class "Default")
      (node (ref "IC14") (pin "27") (pinfunction "GPA6_27") (pintype "bidirectional"))
      (node (ref "Q13") (pin "4") (pinfunction "G_4") (pintype "passive"))
      (node (ref "R69") (pin "2") (pinfunction "2_2") (pintype "passive"))
    )
    (net (code "18") (name "CV_ACTIVE") (class "Default")
      (node (ref "IC14") (pin "23") (pinfunction "GPA2_23") (pintype "bidirectional"))
      (node (ref "Q19") (pin "1") (pinfunction "G_1") (pintype "passive"))
      (node (ref "R90") (pin "1") (pinfunction "1_1") (pintype "passive"))
      (node (ref "R92") (pin "2") (pinfunction "2_2") (pintype "passive"))
    )
    (net (code "19") (name "DC+") (class "Default")
      (node (ref "C1") (pin "2") (pinfunction "2_2") (pintype "passive"))
      (node (ref "L1") (pin "1") (pinfunction "1_1") (pintype "passive"))
      (node (ref "R1") (pin "2") (pinfunction "2_2") (pintype "passive"))
      (node (ref "X1") (pin "1") (pinfunction "1_1") (pintype "passive"))
    )
    (net (code "20") (name "DC-") (class "Default")
      (node (ref "C1") (pin "1") (pinfunction "1_1") (pintype "passive"))
      (node (ref "L1") (pin "3") (pinfunction "1_3") (pintype "passive"))
      (node (ref "R1") (pin "1") (pinfunction "1_1") (pintype "passive"))
      (node (ref "X1") (pin "2") (pinfunction "1_2") (pintype "passive"))
    )
    (net (code "21") (name "DC_OUT") (class "Default")
      (node (ref "C2") (pin "+") (pinfunction "+_+") (pintype "passive"))
      (node (ref "C20") (pin "+") (pinfunction "+_+") (pintype "passive"))
      (node (ref "C4") (pin "2") (pinfunction "2_2") (pintype "passive"))
      (node (ref "C40") (pin "1") (pinfunction "1_1") (pintype "passive"))
      (node (ref "C5") (pin "1") (pinfunction "1_1") (pintype "passive"))
      (node (ref "C6") (pin "1") (pinfunction "1_1") (pintype "passive"))
      (node (ref "C7") (pin "1") (pinfunction "1_1") (pintype "passive"))
      (node (ref "C8") (pin "2") (pinfunction "2_2") (pintype "passive"))
      (node (ref "IC1") (pin "11") (pinfunction "VIN_11") (pintype "passive"))
      (node (ref "IC2") (pin "3") (pinfunction "IN_3") (pintype "input"))
      (node (ref "L1") (pin "2") (pinfunction "2_2") (pintype "passive"))
      (node (ref "Q5") (pin "2") (pinfunction "C_2") (pintype "passive"))
      (node (ref "Q5") (pin "4") (pinfunction "C_4") (pintype "passive"))
      (node (ref "R3") (pin "1") (pinfunction "1_1") (pintype "passive"))
      (node (ref "R35") (pin "2") (pinfunction "2_2") (pintype "passive"))
      (node (ref "R36") (pin "2") (pinfunction "2_2") (pintype "passive"))
      (node (ref "ZD1") (pin "C") (pinfunction "C_C") (pintype "passive"))
    )
    (net (code "22") (name "DIB_5V") (class "Default")
      (node (ref "X2") (pin "23") (pinfunction "1_23") (pintype "passive"))
      (node (ref "X2") (pin "24") (pinfunction "1_24") (pintype "passive"))
    )
    (net (code "23") (name "DIB_12V") (class "Default")
      (node (ref "X2") (pin "21") (pinfunction "1_21") (pintype "passive"))
      (node (ref "X2") (pin "22") (pinfunction "1_22") (pintype "passive"))
    )
    (net (code "24") (name "DIB_A0") (class "Default")
      (node (ref "IC8") (pin "1") (pinfunction "A0_1") (pintype "input"))
      (node (ref "IC9") (pin "7") (pinfunction "A0_7") (pintype "input"))
      (node (ref "R26") (pin "2") (pinfunction "2_2") (pintype "passive"))
      (node (ref "X2") (pin "17") (pinfunction "1_17") (pintype "passive"))
    )
    (net (code "25") (name "DIB_A1") (class "Default")
      (node (ref "IC8") (pin "2") (pinfunction "A1_2") (pintype "input"))
      (node (ref "IC9") (pin "6") (pinfunction "A1_6") (pintype "input"))
      (node (ref "R25") (pin "2") (pinfunction "2_2") (pintype "passive"))
      (node (ref "X2") (pin "19") (pinfunction "1_19") (pintype "passive"))
    )
    (net (code "26") (name "DIB_A2") (class "Default")
      (node (ref "IC8") (pin "3") (pinfunction "A2_3") (pintype "input"))
      (node (ref "IC9") (pin "5") (pinfunction "A2_5") (pintype "input"))
      (node (ref "R24") (pin "2") (pinfunction "2_2") (pintype "passive"))
      (node (ref "X2") (pin "18") (pinfunction "1_18") (pintype "passive"))
    )
    (net (code "27") (name "DIB_CSA") (class "Default")
      (node (ref "IC4") (pin "4") (pinfunction "A2_4") (pintype "input"))
      (node (ref "X2") (pin "9") (pinfunction "1_9") (pintype "passive"))
    )
    (net (code "28") (name "DIB_CSB") (class "Default")
      (node (ref "IC4") (pin "5") (pinfunction "A3_5") (pintype "input"))
      (node (ref "X2") (pin "12") (pinfunction "1_12") (pintype "passive"))
    )
    (net (code "29") (name "DIB_IRQ") (class "Default")
      (node (ref "IC7") (pin "6") (pinfunction "A4_6") (pintype "output"))
      (node (ref "X2") (pin "10") (pinfunction "1_10") (pintype "passive"))
    )
    (net (code "30") (name "DIB_MISO") (class "Default")
      (node (ref "IC4") (pin "6") (pinfunction "A4_6") (pintype "output"))
      (node (ref "X2") (pin "14") (pinfunction "1_14") (pintype "passive"))
    )
    (net (code "31") (name "DIB_MOSI") (class "Default")
      (node (ref "IC7") (pin "3") (pinfunction "A1_3") (pintype "input"))
      (node (ref "X2") (pin "15") (pinfunction "1_15") (pintype "passive"))
    )
    (net (code "32") (name "DIB_NFAULT") (class "Default")
      (node (ref "IC9") (pin "3") (pinfunction "ALERT_3") (pintype "passive"))
      (node (ref "X2") (pin "3") (pinfunction "1_3") (pintype "passive"))
    )
    (net (code "33") (name "DIB_NRESET") (class "Default")
      (node (ref "IC7") (pin "5") (pinfunction "A3_5") (pintype "input"))
      (node (ref "X2") (pin "4") (pinfunction "1_4") (pintype "passive"))
    )
    (net (code "34") (name "DIB_SCL") (class "Default")
      (node (ref "IC8") (pin "6") (pinfunction "SCL_6") (pintype "bidirectional"))
      (node (ref "IC9") (pin "2") (pinfunction "SCL_2") (pintype "bidirectional"))
      (node (ref "X2") (pin "5") (pinfunction "1_5") (pintype "passive"))
    )
    (net (code "35") (name "DIB_SCLK") (class "Default")
      (node (ref "IC4") (pin "3") (pinfunction "A1_3") (pintype "input"))
      (node (ref "X2") (pin "13") (pinfunction "1_13") (pintype "passive"))
    )
    (net (code "36") (name "DIB_SDA") (class "Default")
      (node (ref "IC8") (pin "5") (pinfunction "SDA_5") (pintype "bidirectional"))
      (node (ref "IC9") (pin "1") (pinfunction "SDA_1") (pintype "bidirectional"))
      (node (ref "X2") (pin "8") (pinfunction "1_8") (pintype "passive"))
    )
    (net (code "37") (name "FB") (class "Default")
      (node (ref "C19") (pin "1") (pinfunction "1_1") (pintype "passive"))
      (node (ref "IC1") (pin "5") (pinfunction "VFB_5") (pintype "input"))
      (node (ref "Q2") (pin "C") (pinfunction "C_C") (pintype "passive"))
      (node (ref "R12") (pin "2") (pinfunction "2_2") (pintype "passive"))
      (node (ref "R14") (pin "1") (pinfunction "1_1") (pintype "passive"))
    )
    (net (code "38") (name "GCOM") (class "Default")
      (node (ref "IC11") (pin "6") (pinfunction "-IN_6") (pintype "input"))
      (node (ref "IC11") (pin "7") (pinfunction "OUT_7") (pintype "output"))
      (node (ref "R40") (pin "1") (pinfunction "1_1") (pintype "passive"))
      (node (ref "R59") (pin "1") (pinfunction "1_1") (pintype "passive"))
    )
    (net (code "39") (name "GND") (class "Default")
      (node (ref "C20") (pin "-") (pinfunction "-_-") (pintype "passive"))
      (node (ref "C21") (pin "2") (pinfunction "2_2") (pintype "passive"))
      (node (ref "C22") (pin "-") (pinfunction "-_-") (pintype "passive"))
      (node (ref "C24") (pin "1") (pinfunction "1_1") (pintype "passive"))
      (node (ref "C25") (pin "2") (pinfunction "2_2") (pintype "passive"))
      (node (ref "C26") (pin "2") (pinfunction "2_2") (pintype "passive"))
      (node (ref "C27") (pin "-") (pinfunction "-_-") (pintype "passive"))
      (node (ref "C28") (pin "2") (pinfunction "2_2") (pintype "passive"))
      (node (ref "C29") (pin "1") (pinfunction "1_1") (pintype "passive"))
      (node (ref "C31") (pin "1") (pinfunction "1_1") (pintype "passive"))
      (node (ref "C32") (pin "2") (pinfunction "2_2") (pintype "passive"))
      (node (ref "C33") (pin "1") (pinfunction "1_1") (pintype "passive"))
      (node (ref "C34") (pin "+") (pinfunction "+_+") (pintype "passive"))
      (node (ref "C36") (pin "1") (pinfunction "1_1") (pintype "passive"))
      (node (ref "C39") (pin "2") (pinfunction "2_2") (pintype "passive"))
      (node (ref "C40") (pin "2") (pinfunction "2_2") (pintype "passive"))
      (node (ref "C42") (pin "2") (pinfunction "2_2") (pintype "passive"))
      (node (ref "C49") (pin "1") (pinfunction "1_1") (pintype "passive"))
      (node (ref "C50") (pin "2") (pinfunction "2_2") (pintype "passive"))
      (node (ref "C51") (pin "1") (pinfunction "1_1") (pintype "passive"))
      (node (ref "C52") (pin "1") (pinfunction "1_1") (pintype "passive"))
      (node (ref "C53") (pin "1") (pinfunction "1_1") (pintype "passive"))
      (node (ref "C54") (pin "1") (pinfunction "1_1") (pintype "passive"))
      (node (ref "C55") (pin "1") (pinfunction "1_1") (pintype "passive"))
      (node (ref "C56") (pin "2") (pinfunction "2_2") (pintype "passive"))
      (node (ref "C57") (pin "1") (pinfunction "1_1") (pintype "passive"))
      (node (ref "C58") (pin "1") (pinfunction "1_1") (pintype "passive"))
      (node (ref "C61") (pin "2") (pinfunction "2_2") (pintype "passive"))
      (node (ref "C62") (pin "1") (pinfunction "1_1") (pintype "passive"))
      (node (ref "C63") (pin "2") (pinfunction "2_2") (pintype "passive"))
      (node (ref "C64") (pin "2") (pinfunction "2_2") (pintype "passive"))
      (node (ref "C65") (pin "1") (pinfunction "1_1") (pintype "passive"))
      (node (ref "C66") (pin "-") (pinfunction "-_-") (pintype "passive"))
      (node (ref "C67") (pin "2") (pinfunction "2_2") (pintype "passive"))
      (node (ref "C68") (pin "1") (pinfunction "1_1") (pintype "passive"))
      (node (ref "C69") (pin "1") (pinfunction "1_1") (pintype "passive"))
      (node (ref "C70") (pin "1") (pinfunction "1_1") (pintype "passive"))
      (node (ref "C71") (pin "2") (pinfunction "2_2") (pintype "passive"))
      (node (ref "C72") (pin "1") (pinfunction "1_1") (pintype "passive"))
      (node (ref "C73") (pin "2") (pinfunction "2_2") (pintype "passive"))
      (node (ref "C74") (pin "1") (pinfunction "1_1") (pintype "passive"))
      (node (ref "C75") (pin "1") (pinfunction "1_1") (pintype "passive"))
      (node (ref "C76") (pin "1") (pinfunction "1_1") (pintype "passive"))
      (node (ref "C77") (pin "1") (pinfunction "1_1") (pintype "passive"))
      (node (ref "C78") (pin "1") (pinfunction "1_1") (pintype "passive"))
      (node (ref "C79") (pin "1") (pinfunction "1_1") (pintype "passive"))
      (node (ref "C80") (pin "1") (pinfunction "1_1") (pintype "passive"))
      (node (ref "C81") (pin "2") (pinfunction "2_2") (pintype "passive"))
      (node (ref "C82") (pin "1") (pinfunction "1_1") (pintype "passive"))
      (node (ref "C83") (pin "1") (pinfunction "1_1") (pintype "passive"))
      (node (ref "C84") (pin "1") (pinfunction "1_1") (pintype "passive"))
      (node (ref "C85") (pin "1") (pinfunction "1_1") (pintype "passive"))
      (node (ref "D14") (pin "C") (pinfunction "C_C") (pintype "passive"))
      (node (ref "IC13") (pin "4") (pinfunction "VSS_4") (pintype "power_in"))
      (node (ref "IC14") (pin "10") (pinfunction "VSS_10") (pintype "power_in"))
      (node (ref "IC14") (pin "15") (pinfunction "A0_15") (pintype "input"))
      (node (ref "IC14") (pin "16") (pinfunction "A1_16") (pintype "input"))
      (node (ref "IC14") (pin "17") (pinfunction "A2_17") (pintype "input"))
      (node (ref "IC15") (pin "4") (pinfunction "GND_4") (pintype "passive"))
      (node (ref "IC16") (pin "8") (pinfunction "GND_8") (pintype "power_in"))
      (node (ref "IC17") (pin "2") (pinfunction "GND_2") (pintype "passive"))
      (node (ref "IC18") (pin "3") (pinfunction "CLK_3") (pintype "bidirectional"))
      (node (ref "IC18") (pin "4") (pinfunction "DGND_4") (pintype "passive"))
      (node (ref "IC18") (pin "5") (pinfunction "AVSS_5") (pintype "passive"))
      (node (ref "IC18") (pin "8") (pinfunction "REFN0_8") (pintype "input"))
      (node (ref "IC20") (pin "4") (pinfunction "GND_4") (pintype "passive"))
      (node (ref "IC3") (pin "4") (pinfunction "GND_4") (pintype "passive"))
      (node (ref "IC4") (pin "15") (pinfunction "GND2_15") (pintype "passive"))
      (node (ref "IC4") (pin "9") (pinfunction "GND2_2_9") (pintype "passive"))
      (node (ref "IC5") (pin "4") (pinfunction "GND_4") (pintype "passive"))
      (node (ref "IC6") (pin "14") (pinfunction "MODE_14") (pintype "bidirectional"))
      (node (ref "IC6") (pin "17") (pinfunction "GND_17") (pintype "bidirectional"))
      (node (ref "IC6") (pin "2") (pinfunction "RT_2") (pintype "bidirectional"))
      (node (ref "IC7") (pin "15") (pinfunction "GND2_15") (pintype "passive"))
      (node (ref "IC7") (pin "9") (pinfunction "GND2_2_9") (pintype "passive"))
      (node (ref "Q15") (pin "2") (pinfunction "S_2") (pintype "passive"))
      (node (ref "Q19") (pin "2") (pinfunction "S_2") (pintype "passive"))
      (node (ref "Q20") (pin "2") (pinfunction "S_2") (pintype "passive"))
      (node (ref "Q21") (pin "2") (pinfunction "S_2") (pintype "passive"))
      (node (ref "Q22") (pin "E") (pinfunction "E_E") (pintype "passive"))
      (node (ref "Q24") (pin "E") (pinfunction "E_E") (pintype "passive"))
      (node (ref "Q26") (pin "2") (pinfunction "S_2") (pintype "passive"))
      (node (ref "R100") (pin "1") (pinfunction "1_1") (pintype "passive"))
      (node (ref "R101") (pin "1") (pinfunction "1_1") (pintype "passive"))
      (node (ref "R102") (pin "2") (pinfunction "2_2") (pintype "passive"))
      (node (ref "R109") (pin "1") (pinfunction "1_1") (pintype "passive"))
      (node (ref "R118") (pin "1") (pinfunction "1_1") (pintype "passive"))
      (node (ref "R121") (pin "1") (pinfunction "1_1") (pintype "passive"))
      (node (ref "R16") (pin "2") (pinfunction "2_2") (pintype "passive"))
      (node (ref "R19") (pin "2") (pinfunction "2_2") (pintype "passive"))
      (node (ref "R21") (pin "2") (pinfunction "2_2") (pintype "passive"))
      (node (ref "R22") (pin "1") (pinfunction "1_1") (pintype "passive"))
      (node (ref "R33") (pin "2") (pinfunction "2_2") (pintype "passive"))
      (node (ref "R43") (pin "1") (pinfunction "1_1") (pintype "passive"))
      (node (ref "R44") (pin "1") (pinfunction "1_1") (pintype "passive"))
      (node (ref "R47") (pin "1") (pinfunction "1_1") (pintype "passive"))
      (node (ref "R61") (pin "1") (pinfunction "1_1") (pintype "passive"))
      (node (ref "R69") (pin "1") (pinfunction "1_1") (pintype "passive"))
      (node (ref "R72") (pin "1") (pinfunction "1_1") (pintype "passive"))
      (node (ref "R75") (pin "1") (pinfunction "1_1") (pintype "passive"))
      (node (ref "R77") (pin "1") (pinfunction "1_1") (pintype "passive"))
      (node (ref "R78") (pin "2") (pinfunction "2_2") (pintype "passive"))
      (node (ref "R93") (pin "2") (pinfunction "2_2") (pintype "passive"))
      (node (ref "R97") (pin "1") (pinfunction "1_1") (pintype "passive"))
      (node (ref "SH1") (pin "2") (pinfunction "GND_B_2") (pintype "bidirectional"))
      (node (ref "TP1") (pin "1") (pinfunction "P$1_1") (pintype "bidirectional"))
      (node (ref "TP2") (pin "1") (pinfunction "P$1_1") (pintype "bidirectional"))
      (node (ref "X3") (pin "2") (pinfunction "1_2") (pintype "passive"))
      (node (ref "ZD2") (pin "A") (pinfunction "A_A") (pintype "passive"))
      (node (ref "ZD5") (pin "1") (pinfunction "A_1") (pintype "passive"))
      (node (ref "ZD5") (pin "2") (pinfunction "A_2") (pintype "passive"))
    )
    (net (code "40") (name "GNDIO") (class "Default")
      (node (ref "C23") (pin "2") (pinfunction "2_2") (pintype "passive"))
      (node (ref "C35") (pin "2") (pinfunction "2_2") (pintype "passive"))
      (node (ref "C37") (pin "1") (pinfunction "1_1") (pintype "passive"))
      (node (ref "C38") (pin "2") (pinfunction "2_2") (pintype "passive"))
      (node (ref "IC4") (pin "2") (pinfunction "GND1_2_2") (pintype "passive"))
      (node (ref "IC4") (pin "8") (pinfunction "GND1_8") (pintype "passive"))
      (node (ref "IC7") (pin "2") (pinfunction "GND1_2_2") (pintype "passive"))
      (node (ref "IC7") (pin "8") (pinfunction "GND1_8") (pintype "passive"))
      (node (ref "IC8") (pin "4") (pinfunction "GND_4") (pintype "passive"))
      (node (ref "IC8") (pin "7") (pinfunction "WP_7") (pintype "input"))
      (node (ref "IC9") (pin "4") (pinfunction "GND_4") (pintype "passive"))
      (node (ref "X2") (pin "11") (pinfunction "1_11") (pintype "passive"))
      (node (ref "X2") (pin "16") (pinfunction "1_16") (pintype "passive"))
      (node (ref "X2") (pin "20") (pinfunction "1_20") (pintype "passive"))
      (node (ref "X2") (pin "25") (pinfunction "1_25") (pintype "passive"))
      (node (ref "X2") (pin "26") (pinfunction "1_26") (pintype "passive"))
      (node (ref "X2") (pin "7") (pinfunction "1_7") (pintype "passive"))
    )
    (net (code "41") (name "IRQ") (class "Default")
      (node (ref "IC14") (pin "20") (pinfunction "INTA_20") (pintype "output"))
      (node (ref "RN2") (pin "5") (pinfunction "2_5") (pintype "passive"))
    )
    (net (code "42") (name "ISENSE+") (class "Default")
      (node (ref "IC12") (pin "3") (pinfunction "+IN_3") (pintype "input"))
      (node (ref "R59") (pin "2") (pinfunction "2_2") (pintype "passive"))
      (node (ref "R60") (pin "2") (pinfunction "2_2") (pintype "passive"))
    )
    (net (code "43") (name "ISENSE-") (class "Default")
      (node (ref "IC12") (pin "2") (pinfunction "-IN_2") (pintype "input"))
      (node (ref "R68") (pin "1") (pinfunction "1_1") (pintype "passive"))
      (node (ref "R73") (pin "2") (pinfunction "2_2") (pintype "passive"))
    )
    (net (code "44") (name "I_MON") (class "Default")
      (node (ref "IC12") (pin "6") (pinfunction "OUT_6") (pintype "output"))
      (node (ref "R64") (pin "1") (pinfunction "1_1") (pintype "passive"))
      (node (ref "R68") (pin "2") (pinfunction "2_2") (pintype "passive"))
      (node (ref "R85") (pin "1") (pinfunction "1_1") (pintype "passive"))
    )
    (net (code "45") (name "I_SERVO") (class "Default")
      (node (ref "C59") (pin "2") (pinfunction "2_2") (pintype "passive"))
      (node (ref "D10") (pin "C") (pinfunction "C_C") (pintype "passive"))
      (node (ref "D12") (pin "A") (pinfunction "A_A") (pintype "passive"))
      (node (ref "IC11") (pin "1") (pinfunction "OUT_1") (pintype "output"))
      (node (ref "R106") (pin "1") (pinfunction "1_1") (pintype "passive"))
    )
    (net (code "46") (name "I_SET") (class "Default")
      (node (ref "IC16") (pin "4") (pinfunction "VOUTA_4") (pintype "output"))
      (node (ref "R63") (pin "1") (pinfunction "1_1") (pintype "passive"))
      (node (ref "R80") (pin "1") (pinfunction "1_1") (pintype "passive"))
    )
    (net (code "47") (name "MISO") (class "Default")
      (node (ref "IC14") (pin "14") (pinfunction "SO_14") (pintype "output"))
      (node (ref "IC18") (pin "15") (pinfunction "DOUT/~{DRDY}_15") (pintype "output"))
      (node (ref "RN2") (pin "7") (pinfunction "2_7") (pintype "passive"))
    )
    (net (code "48") (name "MOSI") (class "Default")
      (node (ref "IC14") (pin "13") (pinfunction "SI_13") (pintype "input"))
      (node (ref "IC16") (pin "7") (pinfunction "DIN_7") (pintype "input"))
      (node (ref "IC18") (pin "16") (pinfunction "DIN_16") (pintype "input"))
      (node (ref "RN2") (pin "6") (pinfunction "2_6") (pintype "passive"))
    )
    (net (code "49") (name "Net-(C10-Pad1)") (class "Default")
      (node (ref "C10") (pin "1") (pinfunction "1_1") (pintype "passive"))
      (node (ref "C14") (pin "+") (pinfunction "+_+") (pintype "passive"))
      (node (ref "C16") (pin "1") (pinfunction "1_1") (pintype "passive"))
      (node (ref "L2") (pin "2") (pinfunction "2_2") (pintype "passive"))
      (node (ref "L3") (pin "1") (pinfunction "1_1") (pintype "passive"))
      (node (ref "R10") (pin "1") (pinfunction "1_1") (pintype "passive"))
      (node (ref "R12") (pin "1") (pinfunction "1_1") (pintype "passive"))
      (node (ref "R6") (pin "1") (pinfunction "1_1") (pintype "passive"))
      (node (ref "R9") (pin "1") (pinfunction "1_1") (pintype "passive"))
    )
    (net (code "50") (name "Net-(C11-Pad1)") (class "Default")
      (node (ref "C11") (pin "1") (pinfunction "1_1") (pintype "passive"))
      (node (ref "L3") (pin "2") (pinfunction "2_2") (pintype "passive"))
      (node (ref "L4") (pin "1") (pinfunction "1_1") (pintype "passive"))
      (node (ref "R6") (pin "2") (pinfunction "2_2") (pintype "passive"))
      (node (ref "R7") (pin "1") (pinfunction "1_1") (pintype "passive"))
    )
    (net (code "51") (name "Net-(C13-Pad2)") (class "Default")
      (node (ref "C13") (pin "2") (pinfunction "2_2") (pintype "passive"))
      (node (ref "R8") (pin "2") (pinfunction "2_2") (pintype "passive"))
    )
    (net (code "52") (name "Net-(C18-Pad1)") (class "Default")
      (node (ref "C18") (pin "1") (pinfunction "1_1") (pintype "passive"))
      (node (ref "R11") (pin "1") (pinfunction "1_1") (pintype "passive"))
    )
    (net (code "53") (name "Net-(C19-Pad2)") (class "Default")
      (node (ref "C19") (pin "2") (pinfunction "2_2") (pintype "passive"))
      (node (ref "D3") (pin "A") (pinfunction "A_A") (pintype "passive"))
      (node (ref "Q2") (pin "B") (pinfunction "B_B") (pintype "passive"))
      (node (ref "R10") (pin "2") (pinfunction "2_2") (pintype "passive"))
      (node (ref "R13") (pin "1") (pinfunction "1_1") (pintype "passive"))
    )
    (net (code "54") (name "Net-(C41-Pad2)") (class "Default")
      (node (ref "C41") (pin "2") (pinfunction "2_2") (pintype "passive"))
      (node (ref "R41") (pin "1") (pinfunction "1_1") (pintype "passive"))
    )
    (net (code "55") (name "Net-(C42-Pad1)") (class "Default")
      (node (ref "C42") (pin "1") (pinfunction "1_1") (pintype "passive"))
      (node (ref "R37") (pin "1") (pinfunction "1_1") (pintype "passive"))
    )
    (net (code "56") (name "Net-(C43-Pad1)") (class "Default")
      (node (ref "C43") (pin "1") (pinfunction "1_1") (pintype "passive"))
      (node (ref "R45") (pin "2") (pinfunction "2_2") (pintype "passive"))
      (node (ref "R46") (pin "1") (pinfunction "1_1") (pintype "passive"))
    )
    (net (code "57") (name "Net-(C44-Pad2)") (class "Default")
      (node (ref "C44") (pin "2") (pinfunction "2_2") (pintype "passive"))
      (node (ref "R48") (pin "1") (pinfunction "1_1") (pintype "passive"))
    )
    (net (code "58") (name "Net-(C45-Pad1)") (class "Default")
      (node (ref "C45") (pin "1") (pinfunction "1_1") (pintype "passive"))
      (node (ref "R54") (pin "2") (pinfunction "2_2") (pintype "passive"))
      (node (ref "R55") (pin "1") (pinfunction "1_1") (pintype "passive"))
    )
    (net (code "59") (name "Net-(C46-Pad1)") (class "Default")
      (node (ref "C46") (pin "1") (pinfunction "1_1") (pintype "passive"))
      (node (ref "R56") (pin "2") (pinfunction "2_2") (pintype "passive"))
    )
    (net (code "60") (name "Net-(C47-Pad2)") (class "Default")
      (node (ref "C47") (pin "2") (pinfunction "2_2") (pintype "passive"))
      (node (ref "R57") (pin "1") (pinfunction "1_1") (pintype "passive"))
    )
    (net (code "61") (name "Net-(C48-Pad2)") (class "Default")
      (node (ref "C48") (pin "2") (pinfunction "2_2") (pintype "passive"))
      (node (ref "R58") (pin "1") (pinfunction "1_1") (pintype "passive"))
    )
    (net (code "62") (name "Net-(C59-Pad1)") (class "Default")
      (node (ref "C59") (pin "1") (pinfunction "1_1") (pintype "passive"))
      (node (ref "R66") (pin "1") (pinfunction "1_1") (pintype "passive"))
    )
    (net (code "63") (name "Net-(C60-Pad2)") (class "Default")
      (node (ref "C60") (pin "2") (pinfunction "2_2") (pintype "passive"))
      (node (ref "R70") (pin "1") (pinfunction "1_1") (pintype "passive"))
    )
    (net (code "64") (name "Net-(C86-Pad2)") (class "Default")
      (node (ref "C86") (pin "2") (pinfunction "2_2") (pintype "passive"))
      (node (ref "Q23") (pin "B") (pinfunction "B_B") (pintype "passive"))
      (node (ref "R108") (pin "1") (pinfunction "1_1") (pintype "passive"))
      (node (ref "R111") (pin "2") (pinfunction "2_2") (pintype "passive"))
      (node (ref "R113") (pin "2") (pinfunction "2_2") (pintype "passive"))
    )
    (net (code "65") (name "Net-(C87-Pad1)") (class "Default")
      (node (ref "C87") (pin "1") (pinfunction "1_1") (pintype "passive"))
      (node (ref "Q22") (pin "B") (pinfunction "B_B") (pintype "passive"))
      (node (ref "R109") (pin "2") (pinfunction "2_2") (pintype "passive"))
      (node (ref "R110") (pin "2") (pinfunction "2_2") (pintype "passive"))
    )
    (net (code "66") (name "Net-(C87-Pad2)") (class "Default")
      (node (ref "C87") (pin "2") (pinfunction "2_2") (pintype "passive"))
      (node (ref "Q23") (pin "C") (pinfunction "C_C") (pintype "passive"))
      (node (ref "R110") (pin "1") (pinfunction "1_1") (pintype "passive"))
      (node (ref "R115") (pin "2") (pinfunction "2_2") (pintype "passive"))
    )
    (net (code "67") (name "Net-(C88-Pad2)") (class "Default")
      (node (ref "C88") (pin "2") (pinfunction "2_2") (pintype "passive"))
      (node (ref "R116") (pin "2") (pinfunction "2_2") (pintype "passive"))
    )
    (net (code "68") (name "Net-(C95-Pad1)") (class "Default")
      (node (ref "C95") (pin "1") (pinfunction "1_1") (pintype "passive"))
      (node (ref "Q25") (pin "B") (pinfunction "B_B") (pintype "passive"))
      (node (ref "R117") (pin "1") (pinfunction "1_1") (pintype "passive"))
      (node (ref "R119") (pin "2") (pinfunction "2_2") (pintype "passive"))
    )
    (net (code "69") (name "Net-(D2-C)") (class "Default")
      (node (ref "C13") (pin "1") (pinfunction "1_1") (pintype "passive"))
      (node (ref "D2") (pin "3") (pinfunction "C_3") (pintype "passive"))
      (node (ref "L2") (pin "1") (pinfunction "1_1") (pintype "passive"))
      (node (ref "Q1") (pin "2") (pinfunction "D_2") (pintype "passive"))
    )
    (net (code "70") (name "Net-(D3-PadC)") (class "Default")
      (node (ref "D3") (pin "C") (pinfunction "C_C") (pintype "passive"))
      (node (ref "Q2") (pin "E") (pinfunction "E_E") (pintype "passive"))
      (node (ref "R9") (pin "2") (pinfunction "2_2") (pintype "passive"))
    )
    (net (code "71") (name "Net-(D5-PadC)") (class "Default")
      (node (ref "D5") (pin "C") (pinfunction "C_C") (pintype "passive"))
      (node (ref "ZD4") (pin "C") (pinfunction "C_C") (pintype "passive"))
    )
    (net (code "72") (name "Net-(D6-PadC)") (class "Default")
      (node (ref "D6") (pin "C") (pinfunction "C_C") (pintype "passive"))
      (node (ref "Q7") (pin "2") (pinfunction "C_2") (pintype "passive"))
      (node (ref "Q7") (pin "4") (pinfunction "C_4") (pintype "passive"))
      (node (ref "ZD4") (pin "A") (pinfunction "A_A") (pintype "passive"))
    )
    (net (code "73") (name "Net-(D7-PadC)") (class "Default")
      (node (ref "D7") (pin "C") (pinfunction "C_C") (pintype "passive"))
      (node (ref "ZD3") (pin "C") (pinfunction "C_C") (pintype "passive"))
    )
    (net (code "74") (name "Net-(D10-PadA)") (class "Default")
      (node (ref "D10") (pin "A") (pinfunction "A_A") (pintype "passive"))
      (node (ref "D8") (pin "A") (pinfunction "A_A") (pintype "passive"))
      (node (ref "R50") (pin "1") (pinfunction "1_1") (pintype "passive"))
    )
    (net (code "75") (name "Net-(D13-PadA)") (class "Default")
      (node (ref "D13") (pin "A") (pinfunction "A_A") (pintype "passive"))
      (node (ref "Q18") (pin "B") (pinfunction "B_B") (pintype "passive"))
      (node (ref "R100") (pin "2") (pinfunction "2_2") (pintype "passive"))
      (node (ref "R95") (pin "1") (pinfunction "1_1") (pintype "passive"))
    )
    (net (code "76") (name "Net-(D13-PadC)") (class "Default")
      (node (ref "D13") (pin "C") (pinfunction "C_C") (pintype "passive"))
      (node (ref "D14") (pin "A") (pinfunction "A_A") (pintype "passive"))
    )
    (net (code "77") (name "Net-(D15-C)") (class "Default")
      (node (ref "C86") (pin "1") (pinfunction "1_1") (pintype "passive"))
      (node (ref "C88") (pin "1") (pinfunction "1_1") (pintype "passive"))
      (node (ref "C89") (pin "+") (pinfunction "+_+") (pintype "passive"))
      (node (ref "D15") (pin "3") (pinfunction "C_3") (pintype "passive"))
      (node (ref "F1") (pin "2") (pinfunction "2_2") (pintype "passive"))
      (node (ref "F2") (pin "1") (pinfunction "1_1") (pintype "passive"))
      (node (ref "JP3") (pin "2") (pinfunction "2_2") (pintype "passive"))
      (node (ref "K1") (pin "2") (pinfunction "O_2") (pintype "passive"))
      (node (ref "Q23") (pin "E") (pinfunction "E_E") (pintype "passive"))
      (node (ref "R108") (pin "2") (pinfunction "2_2") (pintype "passive"))
    )
    (net (code "78") (name "Net-(FB1-1)") (class "Default")
      (node (ref "C22") (pin "+") (pinfunction "+_+") (pintype "passive"))
      (node (ref "FB1") (pin "P$1") (pinfunction "1_P$1") (pintype "passive"))
      (node (ref "IC3") (pin "1") (pinfunction "OUT_1") (pintype "output"))
      (node (ref "R18") (pin "1") (pinfunction "1_1") (pintype "passive"))
    )
    (net (code "79") (name "Net-(FB2-1)") (class "Default")
      (node (ref "C26") (pin "1") (pinfunction "1_1") (pintype "passive"))
      (node (ref "C27") (pin "+") (pinfunction "+_+") (pintype "passive"))
      (node (ref "FB2") (pin "P$1") (pinfunction "1_P$1") (pintype "passive"))
      (node (ref "IC6") (pin "12") (pinfunction "LDO+_12") (pintype "bidirectional"))
      (node (ref "R20") (pin "1") (pinfunction "1_1") (pintype "passive"))
    )
    (net (code "80") (name "Net-(IC1-CAP)") (class "Default")
      (node (ref "C8") (pin "1") (pinfunction "1_1") (pintype "passive"))
      (node (ref "IC1") (pin "9") (pinfunction "CAP_9") (pintype "passive"))
    )
    (net (code "81") (name "Net-(IC1-FREQ)") (class "Default")
      (node (ref "IC1") (pin "2") (pinfunction "FREQ_2") (pintype "input"))
      (node (ref "R4") (pin "1") (pinfunction "1_1") (pintype "passive"))
    )
    (net (code "82") (name "Net-(IC1-GATE)") (class "Default")
      (node (ref "IC1") (pin "12") (pinfunction "GATE_12") (pintype "output"))
      (node (ref "R5") (pin "1") (pinfunction "1_1") (pintype "passive"))
    )
    (net (code "83") (name "Net-(IC1-ITH)") (class "Default")
      (node (ref "C17") (pin "1") (pinfunction "1_1") (pintype "passive"))
      (node (ref "IC1") (pin "6") (pinfunction "ITH_6") (pintype "bidirectional"))
      (node (ref "R11") (pin "2") (pinfunction "2_2") (pintype "passive"))
    )
    (net (code "84") (name "Net-(IC1-RUN)") (class "Default")
      (node (ref "D1") (pin "C") (pinfunction "C_C") (pintype "passive"))
      (node (ref "IC1") (pin "8") (pinfunction "RUN_8") (pintype "input"))
      (node (ref "R2") (pin "2") (pinfunction "2_2") (pintype "passive"))
    )
    (net (code "85") (name "Net-(IC1-SENSE)") (class "Default")
      (node (ref "IC1") (pin "10") (pinfunction "SENSE_10") (pintype "input"))
      (node (ref "Q1") (pin "3") (pinfunction "S_3") (pintype "passive"))
      (node (ref "R3") (pin "2") (pinfunction "2_2") (pintype "passive"))
    )
    (net (code "86") (name "Net-(IC1-SS)") (class "Default")
      (node (ref "C9") (pin "2") (pinfunction "2_2") (pintype "passive"))
      (node (ref "IC1") (pin "4") (pinfunction "SS_4") (pintype "input"))
    )
    (net (code "87") (name "Net-(IC2-ADJ)") (class "Default")
      (node (ref "IC2") (pin "1") (pinfunction "ADJ_1") (pintype "passive"))
      (node (ref "R15") (pin "2") (pinfunction "2_2") (pintype "passive"))
      (node (ref "R16") (pin "1") (pinfunction "1_1") (pintype "passive"))
    )
    (net (code "88") (name "Net-(IC3-FB)") (class "Default")
      (node (ref "IC3") (pin "7") (pinfunction "FB_7") (pintype "input"))
      (node (ref "R18") (pin "2") (pinfunction "2_2") (pintype "passive"))
      (node (ref "R19") (pin "1") (pinfunction "1_1") (pintype "passive"))
    )
    (net (code "89") (name "Net-(IC4-B1)") (class "Default")
      (node (ref "IC4") (pin "14") (pinfunction "B1_14") (pintype "output"))
      (node (ref "RN2") (pin "1") (pinfunction "1_1") (pintype "passive"))
    )
    (net (code "90") (name "Net-(IC4-B4)") (class "Default")
      (node (ref "IC4") (pin "11") (pinfunction "B4_11") (pintype "input"))
      (node (ref "RN2") (pin "2") (pinfunction "1_2") (pintype "passive"))
    )
    (net (code "91") (name "Net-(IC5-Y0)") (class "Default")
      (node (ref "IC5") (pin "7") (pinfunction "Y0_7") (pintype "output"))
      (node (ref "RN1") (pin "1") (pinfunction "1_1") (pintype "passive"))
    )
    (net (code "92") (name "Net-(IC5-Y1)") (class "Default")
      (node (ref "IC5") (pin "6") (pinfunction "Y1_6") (pintype "output"))
      (node (ref "RN1") (pin "2") (pinfunction "1_2") (pintype "passive"))
    )
    (net (code "93") (name "Net-(IC5-Y2)") (class "Default")
      (node (ref "IC5") (pin "5") (pinfunction "Y2_5") (pintype "output"))
      (node (ref "RN1") (pin "3") (pinfunction "1_3") (pintype "passive"))
    )
    (net (code "94") (name "Net-(IC6-ADJ+)") (class "Default")
      (node (ref "IC6") (pin "15") (pinfunction "ADJ+_15") (pintype "bidirectional"))
      (node (ref "R20") (pin "2") (pinfunction "2_2") (pintype "passive"))
      (node (ref "R21") (pin "1") (pinfunction "1_1") (pintype "passive"))
    )
    (net (code "95") (name "Net-(IC6-ADJ-)") (class "Default")
      (node (ref "IC6") (pin "4") (pinfunction "ADJ-_4") (pintype "bidirectional"))
      (node (ref "R22") (pin "2") (pinfunction "2_2") (pintype "passive"))
      (node (ref "R23") (pin "1") (pinfunction "1_1") (pintype "passive"))
    )
    (net (code "96") (name "Net-(IC6-BYP+)") (class "Default")
      (node (ref "C29") (pin "2") (pinfunction "2_2") (pintype "passive"))
      (node (ref "IC6") (pin "16") (pinfunction "BYP+_16") (pintype "bidirectional"))
    )
    (net (code "97") (name "Net-(IC6-BYP-)") (class "Default")
      (node (ref "C31") (pin "2") (pinfunction "2_2") (pintype "passive"))
      (node (ref "IC6") (pin "3") (pinfunction "BYP-_3") (pintype "bidirectional"))
    )
    (net (code "98") (name "Net-(IC6-C+)") (class "Default")
      (node (ref "C30") (pin "1") (pinfunction "1_1") (pintype "passive"))
      (node (ref "IC6") (pin "10") (pinfunction "C+_10") (pintype "bidirectional"))
      (node (ref "IC6") (pin "9") (pinfunction "NC1_9") (pintype "bidirectional"))
    )
    (net (code "99") (name "Net-(IC6-C-)") (class "Default")
      (node (ref "C30") (pin "2") (pinfunction "2_2") (pintype "passive"))
      (node (ref "IC6") (pin "7") (pinfunction "C-_7") (pintype "bidirectional"))
      (node (ref "IC6") (pin "8") (pinfunction "NC2_8") (pintype "bidirectional"))
    )
    (net (code "100") (name "Net-(IC7-B1)") (class "Default")
      (node (ref "IC7") (pin "14") (pinfunction "B1_14") (pintype "output"))
      (node (ref "RN2") (pin "3") (pinfunction "1_3") (pintype "passive"))
    )
    (net (code "101") (name "Net-(IC7-B4)") (class "Default")
      (node (ref "IC7") (pin "11") (pinfunction "B4_11") (pintype "input"))
      (node (ref "RN2") (pin "4") (pinfunction "1_4") (pintype "passive"))
    )
    (net (code "102") (name "Net-(IC10A-+IN)") (class "Default")
      (node (ref "IC10") (pin "3") (pinfunction "+IN_3") (pintype "input"))
      (node (ref "R48") (pin "2") (pinfunction "2_2") (pintype "passive"))
      (node (ref "R49") (pin "2") (pinfunction "2_2") (pintype "passive"))
    )
    (net (code "103") (name "Net-(IC10A--IN)") (class "Default")
      (node (ref "D9") (pin "C") (pinfunction "C_C") (pintype "passive"))
      (node (ref "IC10") (pin "2") (pinfunction "-IN_2") (pintype "input"))
      (node (ref "R52") (pin "2") (pinfunction "2_2") (pintype "passive"))
      (node (ref "R56") (pin "1") (pinfunction "1_1") (pintype "passive"))
      (node (ref "R58") (pin "2") (pinfunction "2_2") (pintype "passive"))
    )
    (net (code "104") (name "Net-(IC10B-+IN)") (class "Default")
      (node (ref "IC10") (pin "5") (pinfunction "+IN_5") (pintype "input"))
      (node (ref "R40") (pin "2") (pinfunction "2_2") (pintype "passive"))
      (node (ref "R41") (pin "2") (pinfunction "2_2") (pintype "passive"))
      (node (ref "R45") (pin "1") (pinfunction "1_1") (pintype "passive"))
    )
    (net (code "105") (name "Net-(IC10B--IN)") (class "Default")
      (node (ref "IC10") (pin "6") (pinfunction "-IN_6") (pintype "input"))
      (node (ref "R53") (pin "2") (pinfunction "2_2") (pintype "passive"))
      (node (ref "R54") (pin "1") (pinfunction "1_1") (pintype "passive"))
      (node (ref "R57") (pin "2") (pinfunction "2_2") (pintype "passive"))
    )
    (net (code "106") (name "Net-(IC11A-+IN)") (class "Default")
      (node (ref "IC11") (pin "3") (pinfunction "+IN_3") (pintype "input"))
      (node (ref "R63") (pin "2") (pinfunction "2_2") (pintype "passive"))
    )
    (net (code "107") (name "Net-(IC11A--IN)") (class "Default")
      (node (ref "D12") (pin "C") (pinfunction "C_C") (pintype "passive"))
      (node (ref "IC11") (pin "2") (pinfunction "-IN_2") (pintype "input"))
      (node (ref "R64") (pin "2") (pinfunction "2_2") (pintype "passive"))
      (node (ref "R67") (pin "2") (pinfunction "2_2") (pintype "passive"))
      (node (ref "R70") (pin "2") (pinfunction "2_2") (pintype "passive"))
    )
    (net (code "108") (name "Net-(IC11B-+IN)") (class "Default")
      (node (ref "C39") (pin "1") (pinfunction "1_1") (pintype "passive"))
      (node (ref "IC11") (pin "5") (pinfunction "+IN_5") (pintype "input"))
      (node (ref "R30") (pin "2") (pinfunction "2_2") (pintype "passive"))
      (node (ref "R33") (pin "1") (pinfunction "1_1") (pintype "passive"))
    )
    (net (code "109") (name "Net-(IC13A-Q)") (class "Default")
      (node (ref "IC13") (pin "5") (pinfunction "Q_5") (pintype "output"))
      (node (ref "JP1") (pin "2") (pinfunction "2_2") (pintype "passive"))
      (node (ref "Q15") (pin "1") (pinfunction "G_1") (pintype "passive"))
      (node (ref "R75") (pin "2") (pinfunction "2_2") (pintype "passive"))
    )
    (net (code "110") (name "Net-(IC15-TRIM{slash}NR)") (class "Default")
      (node (ref "C67") (pin "1") (pinfunction "1_1") (pintype "passive"))
      (node (ref "IC15") (pin "5") (pinfunction "TRIM/NR_5") (pintype "input"))
    )
    (net (code "111") (name "Net-(IC17-NO)") (class "Default")
      (node (ref "C72") (pin "2") (pinfunction "2_2") (pintype "passive"))
      (node (ref "IC17") (pin "1") (pinfunction "NO_1") (pintype "bidirectional"))
      (node (ref "R82") (pin "1") (pinfunction "1_1") (pintype "passive"))
      (node (ref "ZD5") (pin "3") (pinfunction "C_3") (pintype "passive"))
    )
    (net (code "112") (name "Net-(IC18-AIN0{slash}REFP1)") (class "Default")
      (node (ref "C74") (pin "2") (pinfunction "2_2") (pintype "passive"))
      (node (ref "IC18") (pin "11") (pinfunction "AIN0/REFP1_11") (pintype "input"))
      (node (ref "R84") (pin "2") (pinfunction "2_2") (pintype "passive"))
    )
    (net (code "113") (name "Net-(IC18-AIN1)") (class "Default")
      (node (ref "C69") (pin "2") (pinfunction "2_2") (pintype "passive"))
      (node (ref "IC18") (pin "10") (pinfunction "AIN1_10") (pintype "input"))
      (node (ref "R80") (pin "2") (pinfunction "2_2") (pintype "passive"))
    )
    (net (code "114") (name "Net-(IC18-AIN2)") (class "Default")
      (node (ref "C70") (pin "2") (pinfunction "2_2") (pintype "passive"))
      (node (ref "IC18") (pin "7") (pinfunction "AIN2_7") (pintype "input"))
      (node (ref "R81") (pin "2") (pinfunction "2_2") (pintype "passive"))
    )
    (net (code "115") (name "Net-(IC18-AIN3{slash}REFN1)") (class "Default")
      (node (ref "C73") (pin "1") (pinfunction "1_1") (pintype "passive"))
      (node (ref "IC18") (pin "6") (pinfunction "AIN3/REFN1_6") (pintype "input"))
      (node (ref "R85") (pin "2") (pinfunction "2_2") (pintype "passive"))
    )
    (net (code "116") (name "Net-(IC18-AVDD)") (class "Default")
      (node (ref "C77") (pin "2") (pinfunction "2_2") (pintype "passive"))
      (node (ref "C78") (pin "2") (pinfunction "2_2") (pintype "passive"))
      (node (ref "IC18") (pin "12") (pinfunction "AVDD_12") (pintype "power_in"))
      (node (ref "R86") (pin "2") (pinfunction "2_2") (pintype "passive"))
    )
    (net (code "117") (name "Net-(IC19A-+IN)") (class "Default")
      (node (ref "IC19") (pin "7") (pinfunction "+IN_7") (pintype "input"))
      (node (ref "IC19") (pin "9") (pinfunction "+IN_9") (pintype "input"))
      (node (ref "R91") (pin "1") (pinfunction "1_1") (pintype "passive"))
      (node (ref "R97") (pin "2") (pinfunction "2_2") (pintype "passive"))
    )
    (net (code "118") (name "Net-(IC19A--IN)") (class "Default")
      (node (ref "IC19") (pin "5") (pinfunction "+IN_5") (pintype "input"))
      (node (ref "IC19") (pin "6") (pinfunction "-IN_6") (pintype "input"))
      (node (ref "R87") (pin "2") (pinfunction "2_2") (pintype "passive"))
    )
    (net (code "119") (name "Net-(IC19A-OUT)") (class "Default")
      (node (ref "IC19") (pin "1") (pinfunction "OUT_1") (pintype "open_collector"))
      (node (ref "IC19") (pin "2") (pinfunction "OUT_2") (pintype "open_collector"))
      (node (ref "R92") (pin "1") (pinfunction "1_1") (pintype "passive"))
    )
    (net (code "120") (name "Net-(IC19B--IN)") (class "Default")
      (node (ref "IC19") (pin "10") (pinfunction "-IN_10") (pintype "input"))
      (node (ref "IC19") (pin "4") (pinfunction "-IN_4") (pintype "input"))
      (node (ref "R102") (pin "1") (pinfunction "1_1") (pintype "passive"))
      (node (ref "R104") (pin "2") (pinfunction "2_2") (pintype "passive"))
    )
    (net (code "121") (name "Net-(IC19C--IN)") (class "Default")
      (node (ref "IC19") (pin "11") (pinfunction "+IN_11") (pintype "input"))
      (node (ref "IC19") (pin "8") (pinfunction "-IN_8") (pintype "input"))
      (node (ref "R106") (pin "2") (pinfunction "2_2") (pintype "passive"))
    )
    (net (code "122") (name "Net-(IC19C-OUT)") (class "Default")
      (node (ref "IC19") (pin "13") (pinfunction "OUT_13") (pintype "open_collector"))
      (node (ref "IC19") (pin "14") (pinfunction "OUT_14") (pintype "open_collector"))
      (node (ref "R105") (pin "1") (pinfunction "1_1") (pintype "passive"))
    )
    (net (code "123") (name "Net-(IC20-+IN)") (class "Default")
      (node (ref "C83") (pin "2") (pinfunction "2_2") (pintype "passive"))
      (node (ref "IC20") (pin "2") (pinfunction "+IN_2") (pintype "input"))
      (node (ref "R88") (pin "2") (pinfunction "2_2") (pintype "passive"))
      (node (ref "R93") (pin "1") (pinfunction "1_1") (pintype "passive"))
    )
    (net (code "124") (name "Net-(IC20--IN)") (class "Default")
      (node (ref "C85") (pin "2") (pinfunction "2_2") (pintype "passive"))
      (node (ref "IC20") (pin "3") (pinfunction "-IN_3") (pintype "input"))
      (node (ref "R99") (pin "2") (pinfunction "2_2") (pintype "passive"))
    )
    (net (code "125") (name "Net-(IC20-OUT)") (class "Default")
      (node (ref "IC20") (pin "7") (pinfunction "OUT_7") (pintype "output"))
      (node (ref "Q21") (pin "1") (pinfunction "G_1") (pintype "passive"))
      (node (ref "R95") (pin "2") (pinfunction "2_2") (pintype "passive"))
    )
    (net (code "126") (name "Net-(K1A--)") (class "Default")
      (node (ref "D16") (pin "A") (pinfunction "A_A") (pintype "passive"))
      (node (ref "K1") (pin "8") (pinfunction "-_8") (pintype "passive"))
      (node (ref "Q26") (pin "3") (pinfunction "D_3") (pintype "passive"))
      (node (ref "R120") (pin "1") (pinfunction "1_1") (pintype "passive"))
    )
    (net (code "127") (name "Net-(K1B-S)") (class "Default")
      (node (ref "K1") (pin "4") (pinfunction "S_4") (pintype "passive"))
      (node (ref "X3") (pin "4") (pinfunction "1_4") (pintype "passive"))
    )
    (net (code "128") (name "Net-(K1C-S)") (class "Default")
      (node (ref "K1") (pin "5") (pinfunction "S_5") (pintype "passive"))
      (node (ref "X3") (pin "5") (pinfunction "1_5") (pintype "passive"))
    )
    (net (code "129") (name "Net-(LED1A-C)") (class "Default")
      (node (ref "LED1") (pin "BC") (pinfunction "C_BC") (pintype "passive"))
      (node (ref "R120") (pin "2") (pinfunction "2_2") (pintype "passive"))
    )
    (net (code "130") (name "Net-(LED1B-C)") (class "Default")
      (node (ref "LED1") (pin "TC") (pinfunction "C_TC") (pintype "passive"))
      (node (ref "R77") (pin "2") (pinfunction "2_2") (pintype "passive"))
    )
    (net (code "131") (name "Net-(LED2-C)") (class "Default")
      (node (ref "LED2") (pin "CC") (pinfunction "C_CC") (pintype "passive"))
      (node (ref "R78") (pin "1") (pinfunction "1_1") (pintype "passive"))
    )
    (net (code "132") (name "Net-(LED3A-C)") (class "Default")
      (node (ref "LED3") (pin "BC") (pinfunction "C_BC") (pintype "passive"))
      (node (ref "R98") (pin "2") (pinfunction "2_2") (pintype "passive"))
    )
    (net (code "133") (name "Net-(LED3B-C)") (class "Default")
      (node (ref "LED3") (pin "TC") (pinfunction "C_TC") (pintype "passive"))
      (node (ref "R94") (pin "1") (pinfunction "1_1") (pintype "passive"))
    )
    (net (code "134") (name "Net-(LED4-PadA)") (class "Default")
      (node (ref "LED4") (pin "A") (pinfunction "A_A") (pintype "passive"))
      (node (ref "R107") (pin "2") (pinfunction "2_2") (pintype "passive"))
    )
    (net (code "135") (name "Net-(Q1-G)") (class "Default")
      (node (ref "Q1") (pin "1") (pinfunction "G_1") (pintype "passive"))
      (node (ref "R5") (pin "2") (pinfunction "2_2") (pintype "passive"))
    )
    (net (code "136") (name "Net-(Q3-G)") (class "Default")
      (node (ref "D4") (pin "C") (pinfunction "C_C") (pintype "passive"))
      (node (ref "D5") (pin "A") (pinfunction "A_A") (pintype "passive"))
      (node (ref "Q3") (pin "1") (pinfunction "G_1") (pintype "passive"))
      (node (ref "R27") (pin "1") (pinfunction "1_1") (pintype "passive"))
    )
    (net (code "137") (name "Net-(Q4-PadB)") (class "Default")
      (node (ref "Q4") (pin "B") (pinfunction "B_B") (pintype "passive"))
      (node (ref "R31") (pin "2") (pinfunction "2_2") (pintype "passive"))
    )
    (net (code "138") (name "Net-(Q5-B)") (class "Default")
      (node (ref "D7") (pin "A") (pinfunction "A_A") (pintype "passive"))
      (node (ref "Q5") (pin "1") (pinfunction "B_1") (pintype "passive"))
      (node (ref "R37") (pin "2") (pinfunction "2_2") (pintype "passive"))
      (node (ref "R38") (pin "1") (pinfunction "1_1") (pintype "passive"))
    )
    (net (code "139") (name "Net-(Q5-E)") (class "Default")
      (node (ref "D4") (pin "A") (pinfunction "A_A") (pintype "passive"))
      (node (ref "Q5") (pin "3") (pinfunction "E_3") (pintype "passive"))
    )
    (net (code "140") (name "Net-(Q6-G)") (class "Default")
      (node (ref "D6") (pin "A") (pinfunction "A_A") (pintype "passive"))
      (node (ref "Q4") (pin "C") (pinfunction "C_C") (pintype "passive"))
      (node (ref "Q6") (pin "1") (pinfunction "G_1") (pintype "passive"))
      (node (ref "R32") (pin "2") (pinfunction "2_2") (pintype "passive"))
    )
    (net (code "141") (name "Net-(Q6-S)") (class "Default")
      (node (ref "Q6") (pin "3") (pinfunction "S_3") (pintype "passive"))
      (node (ref "R28") (pin "1") (pinfunction "1_1") (pintype "passive"))
      (node (ref "R29") (pin "1") (pinfunction "1_1") (pintype "passive"))
      (node (ref "R31") (pin "1") (pinfunction "1_1") (pintype "passive"))
      (node (ref "R32") (pin "1") (pinfunction "1_1") (pintype "passive"))
    )
    (net (code "142") (name "Net-(Q7-E)") (class "Default")
      (node (ref "Q7") (pin "3") (pinfunction "E_3") (pintype "passive"))
      (node (ref "R42") (pin "1") (pinfunction "1_1") (pintype "passive"))
    )
    (net (code "143") (name "Net-(Q8-PadE)") (class "Default")
      (node (ref "Q8") (pin "E") (pinfunction "E_E") (pintype "passive"))
      (node (ref "R35") (pin "1") (pinfunction "1_1") (pintype "passive"))
    )
    (net (code "144") (name "Net-(Q9-PadE)") (class "Default")
      (node (ref "Q9") (pin "E") (pinfunction "E_E") (pintype "passive"))
      (node (ref "R36") (pin "1") (pinfunction "1_1") (pintype "passive"))
    )
    (net (code "145") (name "Net-(Q10-PadB)") (class "Default")
      (node (ref "Q10") (pin "B") (pinfunction "B_B") (pintype "passive"))
      (node (ref "R34") (pin "1") (pinfunction "1_1") (pintype "passive"))
      (node (ref "R43") (pin "2") (pinfunction "2_2") (pintype "passive"))
      (node (ref "R44") (pin "2") (pinfunction "2_2") (pintype "passive"))
    )
    (net (code "146") (name "Net-(Q10-PadE)") (class "Default")
      (node (ref "Q10") (pin "E") (pinfunction "E_E") (pintype "passive"))
      (node (ref "R50") (pin "2") (pinfunction "2_2") (pintype "passive"))
    )
    (net (code "147") (name "Net-(Q11-PadC)") (class "Default")
      (node (ref "Q11") (pin "C") (pinfunction "C_C") (pintype "passive"))
      (node (ref "Q8") (pin "B") (pinfunction "B_B") (pintype "passive"))
      (node (ref "Q8") (pin "C") (pinfunction "C_C") (pintype "passive"))
      (node (ref "Q9") (pin "B") (pinfunction "B_B") (pintype "passive"))
    )
    (net (code "148") (name "Net-(Q11-PadE)") (class "Default")
      (node (ref "Q11") (pin "E") (pinfunction "E_E") (pintype "passive"))
      (node (ref "R51") (pin "2") (pinfunction "2_2") (pintype "passive"))
    )
    (net (code "149") (name "Net-(Q12-S-Pad1)") (class "Default")
      (node (ref "Q12") (pin "1") (pinfunction "S_1") (pintype "passive"))
      (node (ref "Q12") (pin "2") (pinfunction "S_2") (pintype "passive"))
      (node (ref "Q12") (pin "3") (pinfunction "S_3") (pintype "passive"))
      (node (ref "R60") (pin "1") (pinfunction "1_1") (pintype "passive"))
      (node (ref "R62") (pin "1") (pinfunction "1_1") (pintype "passive"))
    )
    (net (code "150") (name "Net-(Q13-S-Pad1)") (class "Default")
      (node (ref "Q13") (pin "1") (pinfunction "S_1") (pintype "passive"))
      (node (ref "Q13") (pin "2") (pinfunction "S_2") (pintype "passive"))
      (node (ref "Q13") (pin "3") (pinfunction "S_3") (pintype "passive"))
      (node (ref "R62") (pin "2") (pinfunction "2_2") (pintype "passive"))
      (node (ref "R65") (pin "2") (pinfunction "2_2") (pintype "passive"))
    )
    (net (code "151") (name "Net-(Q14-S-Pad1)") (class "Default")
      (node (ref "Q14") (pin "1") (pinfunction "S_1") (pintype "passive"))
      (node (ref "Q14") (pin "2") (pinfunction "S_2") (pintype "passive"))
      (node (ref "Q14") (pin "3") (pinfunction "S_3") (pintype "passive"))
      (node (ref "R71") (pin "2") (pinfunction "2_2") (pintype "passive"))
    )
    (net (code "152") (name "Net-(Q16-D)") (class "Default")
      (node (ref "Q16") (pin "3") (pinfunction "D_3") (pintype "passive"))
      (node (ref "R79") (pin "2") (pinfunction "2_2") (pintype "passive"))
    )
    (net (code "153") (name "Net-(Q17-PadA2)") (class "Default")
      (node (ref "Q17") (pin "A2") (pinfunction "A2_A2") (pintype "passive"))
      (node (ref "R96") (pin "2") (pinfunction "2_2") (pintype "passive"))
    )
    (net (code "154") (name "Net-(Q17-PadG)") (class "Default")
      (node (ref "Q17") (pin "G") (pinfunction "G_G") (pintype "passive"))
      (node (ref "Q18") (pin "C") (pinfunction "C_C") (pintype "passive"))
      (node (ref "R89") (pin "1") (pinfunction "1_1") (pintype "passive"))
    )
    (net (code "155") (name "Net-(Q18-PadE)") (class "Default")
      (node (ref "Q18") (pin "E") (pinfunction "E_E") (pintype "passive"))
      (node (ref "R101") (pin "2") (pinfunction "2_2") (pintype "passive"))
    )
    (net (code "156") (name "Net-(Q19-D)") (class "Default")
      (node (ref "Q19") (pin "3") (pinfunction "D_3") (pintype "passive"))
      (node (ref "R94") (pin "2") (pinfunction "2_2") (pintype "passive"))
    )
    (net (code "157") (name "Net-(Q20-D)") (class "Default")
      (node (ref "Q20") (pin "3") (pinfunction "D_3") (pintype "passive"))
      (node (ref "R98") (pin "1") (pinfunction "1_1") (pintype "passive"))
    )
    (net (code "158") (name "Net-(Q24-PadB)") (class "Default")
      (node (ref "Q24") (pin "B") (pinfunction "B_B") (pintype "passive"))
      (node (ref "R115") (pin "1") (pinfunction "1_1") (pintype "passive"))
      (node (ref "R118") (pin "2") (pinfunction "2_2") (pintype "passive"))
    )
    (net (code "159") (name "Net-(Q25-PadC)") (class "Default")
      (node (ref "Q25") (pin "C") (pinfunction "C_C") (pintype "passive"))
      (node (ref "R112") (pin "1") (pinfunction "1_1") (pintype "passive"))
    )
    (net (code "160") (name "Net-(R65-Pad1)") (class "Default")
      (node (ref "R65") (pin "1") (pinfunction "1_1") (pintype "passive"))
      (node (ref "R71") (pin "2S") (pinfunction "2S_2S") (pintype "passive"))
    )
    (net (code "161") (name "Net-(R66-Pad2)") (class "Default")
      (node (ref "R66") (pin "2") (pinfunction "2_2") (pintype "passive"))
      (node (ref "R67") (pin "1") (pinfunction "1_1") (pintype "passive"))
    )
    (net (code "162") (name "Net-(R71-Pad1S)") (class "Default")
      (node (ref "R71") (pin "1S") (pinfunction "1S_1S") (pintype "passive"))
      (node (ref "R73") (pin "1") (pinfunction "1_1") (pintype "passive"))
    )
    (net (code "163") (name "Net-(R82-Pad2)") (class "Default")
      (node (ref "R82") (pin "2") (pinfunction "2_2") (pintype "passive"))
      (node (ref "R83") (pin "1") (pinfunction "1_1") (pintype "passive"))
    )
    (net (code "164") (name "Net-(R83-Pad2)") (class "Default")
      (node (ref "R83") (pin "2") (pinfunction "2_2") (pintype "passive"))
      (node (ref "X3") (pin "1") (pinfunction "1_1") (pintype "passive"))
    )
    (net (code "165") (name "Net-(R112-Pad2)") (class "Default")
      (node (ref "R112") (pin "2") (pinfunction "2_2") (pintype "passive"))
      (node (ref "R113") (pin "1") (pinfunction "1_1") (pintype "passive"))
    )
    (net (code "166") (name "OE_GREEN") (class "Default")
      (node (ref "IC14") (pin "7") (pinfunction "GPB6_7") (pintype "bidirectional"))
      (node (ref "LED2") (pin "GREEN") (pinfunction "AG_GREEN") (pintype "passive"))
    )
    (net (code "167") (name "OE_RED") (class "Default")
      (node (ref "IC14") (pin "8") (pinfunction "GPB7_8") (pintype "bidirectional"))
      (node (ref "LED2") (pin "RED") (pinfunction "AR_RED") (pintype "passive"))
    )
    (net (code "168") (name "OE_SYNC") (class "Default")
      (node (ref "IC7") (pin "4") (pinfunction "A2_4") (pintype "input"))
      (node (ref "X2") (pin "6") (pinfunction "1_6") (pintype "passive"))
    )
    (net (code "169") (name "OE_TRIG") (class "Default")
      (node (ref "IC13") (pin "1") (pinfunction "CLK_1") (pintype "input"))
      (node (ref "IC7") (pin "13") (pinfunction "B2_13") (pintype "output"))
    )
    (net (code "170") (name "OUTC+") (class "Default")
      (node (ref "C90") (pin "1") (pinfunction "1_1") (pintype "passive"))
      (node (ref "C91") (pin "+") (pinfunction "+_+") (pintype "passive"))
      (node (ref "C92") (pin "1") (pinfunction "1_1") (pintype "passive"))
      (node (ref "C93") (pin "1") (pinfunction "1_1") (pintype "passive"))
      (node (ref "J2") (pin "1") (pinfunction "1_1") (pintype "passive"))
      (node (ref "J2") (pin "NC1") (pinfunction "1_NC1") (pintype "passive"))
      (node (ref "J2") (pin "NC2") (pinfunction "1_NC2") (pintype "passive"))
      (node (ref "J2") (pin "NC3") (pinfunction "1_NC3") (pintype "passive"))
      (node (ref "J2") (pin "NC4") (pinfunction "1_NC4") (pintype "passive"))
      (node (ref "X4") (pin "1") (pinfunction "1_1") (pintype "passive"))
      (node (ref "X4") (pin "2") (pinfunction "1_2") (pintype "passive"))
      (node (ref "X4") (pin "3") (pinfunction "1_3") (pintype "passive"))
      (node (ref "X4") (pin "4") (pinfunction "1_4") (pintype "passive"))
      (node (ref "X4") (pin "5") (pinfunction "1_5") (pintype "passive"))
    )
    (net (code "171") (name "OUTC-") (class "Default")
      (node (ref "C91") (pin "-") (pinfunction "-_-") (pintype "passive"))
      (node (ref "C92") (pin "2") (pinfunction "2_2") (pintype "passive"))
      (node (ref "C93") (pin "2") (pinfunction "2_2") (pintype "passive"))
      (node (ref "C94") (pin "2") (pinfunction "2_2") (pintype "passive"))
      (node (ref "J3") (pin "1") (pinfunction "1_1") (pintype "passive"))
      (node (ref "J3") (pin "NC1") (pinfunction "1_NC1") (pintype "passive"))
      (node (ref "J3") (pin "NC2") (pinfunction "1_NC2") (pintype "passive"))
      (node (ref "J3") (pin "NC3") (pinfunction "1_NC3") (pintype "passive"))
      (node (ref "J3") (pin "NC4") (pinfunction "1_NC4") (pintype "passive"))
      (node (ref "X4") (pin "16") (pinfunction "1_16") (pintype "passive"))
      (node (ref "X4") (pin "17") (pinfunction "1_17") (pintype "passive"))
      (node (ref "X4") (pin "18") (pinfunction "1_18") (pintype "passive"))
      (node (ref "X4") (pin "19") (pinfunction "1_19") (pintype "passive"))
      (node (ref "X4") (pin "20") (pinfunction "1_20") (pintype "passive"))
    )
    (net (code "172") (name "OUTF+") (class "Default")
      (node (ref "F2") (pin "2") (pinfunction "2_2") (pintype "passive"))
      (node (ref "Q17") (pin "A1") (pinfunction "A1_A1") (pintype "passive"))
      (node (ref "R89") (pin "2") (pinfunction "2_2") (pintype "passive"))
      (node (ref "X4") (pin "10") (pinfunction "1_10") (pintype "passive"))
      (node (ref "X4") (pin "6") (pinfunction "1_6") (pintype "passive"))
      (node (ref "X4") (pin "7") (pinfunction "1_7") (pintype "passive"))
      (node (ref "X4") (pin "8") (pinfunction "1_8") (pintype "passive"))
      (node (ref "X4") (pin "9") (pinfunction "1_9") (pintype "passive"))
    )
    (net (code "173") (name "OVP_EN") (class "Default")
      (node (ref "IC14") (pin "5") (pinfunction "GPB4_5") (pintype "bidirectional"))
      (node (ref "IC20") (pin "6") (pinfunction "~{SHDN}_6") (pintype "input"))
    )
    (net (code "174") (name "PE") (class "Default")
      (node (ref "C3") (pin "2") (pinfunction "2_2") (pintype "passive"))
      (node (ref "C4") (pin "1") (pinfunction "1_1") (pintype "passive"))
      (node (ref "C90") (pin "2") (pinfunction "2_2") (pintype "passive"))
      (node (ref "C94") (pin "1") (pinfunction "1_1") (pintype "passive"))
      (node (ref "J1") (pin "1") (pinfunction "P$1_1") (pintype "bidirectional"))
      (node (ref "J1") (pin "2") (pinfunction "P$1_2") (pintype "bidirectional"))
      (node (ref "X3") (pin "3") (pinfunction "1_3") (pintype "passive"))
    )
    (net (code "175") (name "POST_OE") (class "Default")
      (node (ref "Q15") (pin "3") (pinfunction "D_3") (pintype "passive"))
      (node (ref "R51") (pin "1") (pinfunction "1_1") (pintype "passive"))
    )
    (net (code "176") (name "POST_OUT+") (class "Default")
      (node (ref "C43") (pin "2") (pinfunction "2_2") (pintype "passive"))
      (node (ref "C48") (pin "1") (pinfunction "1_1") (pintype "passive"))
      (node (ref "C60") (pin "1") (pinfunction "1_1") (pintype "passive"))
      (node (ref "F1") (pin "1") (pinfunction "1_1") (pintype "passive"))
      (node (ref "Q3") (pin "3") (pinfunction "S_3") (pintype "passive"))
      (node (ref "Q4") (pin "E") (pinfunction "E_E") (pintype "passive"))
      (node (ref "R13") (pin "2") (pinfunction "2_2") (pintype "passive"))
      (node (ref "R27") (pin "2") (pinfunction "2_2") (pintype "passive"))
      (node (ref "R28") (pin "2") (pinfunction "2_2") (pintype "passive"))
      (node (ref "R29") (pin "2") (pinfunction "2_2") (pintype "passive"))
      (node (ref "R34") (pin "2") (pinfunction "2_2") (pintype "passive"))
      (node (ref "ZD3") (pin "A") (pinfunction "A_A") (pintype "passive"))
    )
    (net (code "177") (name "POST_OUT-") (class "Default")
      (node (ref "C44") (pin "1") (pinfunction "1_1") (pintype "passive"))
      (node (ref "C45") (pin "2") (pinfunction "2_2") (pintype "passive"))
      (node (ref "C89") (pin "-") (pinfunction "-_-") (pintype "passive"))
      (node (ref "C95") (pin "2") (pinfunction "2_2") (pintype "passive"))
      (node (ref "D11") (pin "A") (pinfunction "A_A") (pintype "passive"))
      (node (ref "D15") (pin "1") (pinfunction "A_1") (pintype "passive"))
      (node (ref "D15") (pin "2") (pinfunction "A_2") (pintype "passive"))
      (node (ref "JP4") (pin "1") (pinfunction "1_1") (pintype "passive"))
      (node (ref "K1") (pin "7") (pinfunction "O_7") (pintype "passive"))
      (node (ref "Q12") (pin "MB") (pinfunction "D_MB") (pintype "passive"))
      (node (ref "Q13") (pin "MB") (pinfunction "D_MB") (pintype "passive"))
      (node (ref "Q14") (pin "MB") (pinfunction "D_MB") (pintype "passive"))
      (node (ref "Q25") (pin "E") (pinfunction "E_E") (pintype "passive"))
      (node (ref "R116") (pin "1") (pinfunction "1_1") (pintype "passive"))
      (node (ref "R119") (pin "1") (pinfunction "1_1") (pintype "passive"))
      (node (ref "X4") (pin "11") (pinfunction "1_11") (pintype "passive"))
      (node (ref "X4") (pin "12") (pinfunction "1_12") (pintype "passive"))
      (node (ref "X4") (pin "13") (pinfunction "1_13") (pintype "passive"))
      (node (ref "X4") (pin "14") (pinfunction "1_14") (pintype "passive"))
      (node (ref "X4") (pin "15") (pinfunction "1_15") (pintype "passive"))
    )
    (net (code "178") (name "PREG_IN-") (class "Default")
      (node (ref "C10") (pin "2") (pinfunction "2_2") (pintype "passive"))
      (node (ref "C14") (pin "-") (pinfunction "-_-") (pintype "passive"))
      (node (ref "C16") (pin "2") (pinfunction "2_2") (pintype "passive"))
      (node (ref "C2") (pin "-") (pinfunction "-_-") (pintype "passive"))
      (node (ref "C3") (pin "1") (pinfunction "1_1") (pintype "passive"))
      (node (ref "C5") (pin "2") (pinfunction "2_2") (pintype "passive"))
      (node (ref "C6") (pin "2") (pinfunction "2_2") (pintype "passive"))
      (node (ref "C7") (pin "2") (pinfunction "2_2") (pintype "passive"))
      (node (ref "D2") (pin "1") (pinfunction "A_1") (pintype "passive"))
      (node (ref "D2") (pin "2") (pinfunction "A_2") (pintype "passive"))
      (node (ref "IC1") (pin "TP") (pinfunction "PGND_TP") (pintype "passive"))
      (node (ref "L1") (pin "4") (pinfunction "2_4") (pintype "passive"))
      (node (ref "R2") (pin "1") (pinfunction "1_1") (pintype "passive"))
      (node (ref "R8") (pin "1") (pinfunction "1_1") (pintype "passive"))
      (node (ref "SH1") (pin "1") (pinfunction "GND_A_1") (pintype "bidirectional"))
      (node (ref "SH2") (pin "2") (pinfunction "GND_B_2") (pintype "bidirectional"))
      (node (ref "SH3") (pin "2") (pinfunction "GND_B_2") (pintype "bidirectional"))
      (node (ref "ZD1") (pin "A") (pinfunction "A_A") (pintype "passive"))
    )
    (net (code "179") (name "PREG_OUT+") (class "Default")
      (node (ref "C12") (pin "1") (pinfunction "1_1") (pintype "passive"))
      (node (ref "C15") (pin "+") (pinfunction "+_+") (pintype "passive"))
      (node (ref "L4") (pin "2") (pinfunction "2_2") (pintype "passive"))
      (node (ref "Q3") (pin "2") (pinfunction "D_2") (pintype "passive"))
      (node (ref "R7") (pin "2") (pinfunction "2_2") (pintype "passive"))
    )
    (net (code "180") (name "PREG_OUT-") (class "Default")
      (node (ref "C11") (pin "2") (pinfunction "2_2") (pintype "passive"))
      (node (ref "C12") (pin "2") (pinfunction "2_2") (pintype "passive"))
      (node (ref "C15") (pin "-") (pinfunction "-_-") (pintype "passive"))
      (node (ref "D11") (pin "C") (pinfunction "C_C") (pintype "passive"))
      (node (ref "Q6") (pin "2") (pinfunction "D_2") (pintype "passive"))
      (node (ref "R71") (pin "1") (pinfunction "1_1") (pintype "passive"))
      (node (ref "R96") (pin "1") (pinfunction "1_1") (pintype "passive"))
      (node (ref "SH2") (pin "1") (pinfunction "GND_A_1") (pintype "bidirectional"))
    )
    (net (code "181") (name "PRE_OE") (class "Default")
      (node (ref "D1") (pin "A") (pinfunction "A_A") (pintype "passive"))
      (node (ref "IC13") (pin "2") (pinfunction "D_2") (pintype "input"))
      (node (ref "IC14") (pin "2") (pinfunction "GPB1_2") (pintype "bidirectional"))
      (node (ref "JP1") (pin "1") (pinfunction "1_1") (pintype "passive"))
    )
    (net (code "182") (name "PWRGOOD") (class "Default")
      (node (ref "IC14") (pin "24") (pinfunction "GPA3_24") (pintype "bidirectional"))
      (node (ref "IC3") (pin "5") (pinfunction "~{ERROR}_5") (pintype "input"))
      (node (ref "R17") (pin "2") (pinfunction "2_2") (pintype "passive"))
    )
    (net (code "183") (name "RSENSE") (class "Default")
      (node (ref "IC14") (pin "3") (pinfunction "GPB2_3") (pintype "bidirectional"))
      (node (ref "Q26") (pin "1") (pinfunction "G_1") (pintype "passive"))
      (node (ref "R121") (pin "2") (pinfunction "2_2") (pintype "passive"))
    )
    (net (code "184") (name "SCLK") (class "Default")
      (node (ref "IC14") (pin "12") (pinfunction "SCK_12") (pintype "input"))
      (node (ref "IC16") (pin "6") (pinfunction "SCLK_6") (pintype "input"))
      (node (ref "IC18") (pin "1") (pinfunction "SCLK_1") (pintype "input"))
      (node (ref "RN2") (pin "8") (pinfunction "2_8") (pintype "passive"))
    )
    (net (code "185") (name "SENSE+") (class "Default")
      (node (ref "C41") (pin "1") (pinfunction "1_1") (pintype "passive"))
      (node (ref "JP3") (pin "1") (pinfunction "1_1") (pintype "passive"))
      (node (ref "K1") (pin "3") (pinfunction "P_3") (pintype "passive"))
      (node (ref "R111") (pin "1") (pinfunction "1_1") (pintype "passive"))
      (node (ref "R46") (pin "2") (pinfunction "2_2") (pintype "passive"))
    )
    (net (code "186") (name "SENSE-") (class "Default")
      (node (ref "C47") (pin "1") (pinfunction "1_1") (pintype "passive"))
      (node (ref "JP4") (pin "2") (pinfunction "2_2") (pintype "passive"))
      (node (ref "K1") (pin "6") (pinfunction "P_6") (pintype "passive"))
      (node (ref "R117") (pin "2") (pinfunction "2_2") (pintype "passive"))
      (node (ref "R55") (pin "2") (pinfunction "2_2") (pintype "passive"))
    )
    (net (code "187") (name "SENSE_ERR") (class "Default")
      (node (ref "IC14") (pin "21") (pinfunction "GPA0_21") (pintype "bidirectional"))
      (node (ref "Q24") (pin "C") (pinfunction "C_C") (pintype "passive"))
      (node (ref "R114") (pin "1") (pinfunction "1_1") (pintype "passive"))
    )
    (net (code "188") (name "SENSE_PROT") (class "Default")
      (node (ref "Q10") (pin "C") (pinfunction "C_C") (pintype "passive"))
      (node (ref "Q22") (pin "C") (pinfunction "C_C") (pintype "passive"))
      (node (ref "Q9") (pin "C") (pinfunction "C_C") (pintype "passive"))
      (node (ref "R38") (pin "2") (pinfunction "2_2") (pintype "passive"))
      (node (ref "R47") (pin "2") (pinfunction "2_2") (pintype "passive"))
    )
    (net (code "189") (name "SGND") (class "Default")
      (node (ref "C17") (pin "2") (pinfunction "2_2") (pintype "passive"))
      (node (ref "C18") (pin "2") (pinfunction "2_2") (pintype "passive"))
      (node (ref "C9") (pin "1") (pinfunction "1_1") (pintype "passive"))
      (node (ref "IC1") (pin "3") (pinfunction "SGND_3") (pintype "passive"))
      (node (ref "R14") (pin "2") (pinfunction "2_2") (pintype "passive"))
      (node (ref "R4") (pin "2") (pinfunction "2_2") (pintype "passive"))
      (node (ref "SH3") (pin "1") (pinfunction "GND_A_1") (pintype "bidirectional"))
    )
    (net (code "190") (name "U_MON") (class "Default")
      (node (ref "IC10") (pin "7") (pinfunction "OUT_7") (pintype "output"))
      (node (ref "R52") (pin "1") (pinfunction "1_1") (pintype "passive"))
      (node (ref "R53") (pin "1") (pinfunction "1_1") (pintype "passive"))
      (node (ref "R84") (pin "1") (pinfunction "1_1") (pintype "passive"))
      (node (ref "R88") (pin "1") (pinfunction "1_1") (pintype "passive"))
    )
    (net (code "191") (name "U_SERVO") (class "Default")
      (node (ref "C46") (pin "2") (pinfunction "2_2") (pintype "passive"))
      (node (ref "D8") (pin "C") (pinfunction "C_C") (pintype "passive"))
      (node (ref "D9") (pin "A") (pinfunction "A_A") (pintype "passive"))
      (node (ref "IC10") (pin "1") (pinfunction "OUT_1") (pintype "output"))
      (node (ref "R87") (pin "1") (pinfunction "1_1") (pintype "passive"))
    )
    (net (code "192") (name "U_SET") (class "Default")
      (node (ref "IC16") (pin "3") (pinfunction "VOUTB_3") (pintype "output"))
      (node (ref "IC17") (pin "3") (pinfunction "NC_3") (pintype "bidirectional"))
      (node (ref "JP2") (pin "1") (pinfunction "1_1") (pintype "passive"))
      (node (ref "R81") (pin "1") (pinfunction "1_1") (pintype "passive"))
      (node (ref "R99") (pin "1") (pinfunction "1_1") (pintype "passive"))
    )
    (net (code "193") (name "U_SET_OUT") (class "Default")
      (node (ref "IC17") (pin "4") (pinfunction "COM_4") (pintype "bidirectional"))
      (node (ref "JP2") (pin "2") (pinfunction "2_2") (pintype "passive"))
      (node (ref "R49") (pin "1") (pinfunction "1_1") (pintype "passive"))
    )
    (net (code "194") (name "V+") (class "Default")
      (node (ref "C49") (pin "2") (pinfunction "2_2") (pintype "passive"))
      (node (ref "C50") (pin "1") (pinfunction "1_1") (pintype "passive"))
      (node (ref "C51") (pin "2") (pinfunction "2_2") (pintype "passive"))
      (node (ref "C52") (pin "2") (pinfunction "2_2") (pintype "passive"))
      (node (ref "C53") (pin "2") (pinfunction "2_2") (pintype "passive"))
      (node (ref "C63") (pin "1") (pinfunction "1_1") (pintype "passive"))
      (node (ref "C64") (pin "1") (pinfunction "1_1") (pintype "passive"))
      (node (ref "C65") (pin "2") (pinfunction "2_2") (pintype "passive"))
      (node (ref "C71") (pin "1") (pinfunction "1_1") (pintype "passive"))
      (node (ref "C80") (pin "2") (pinfunction "2_2") (pintype "passive"))
      (node (ref "C81") (pin "1") (pinfunction "1_1") (pintype "passive"))
      (node (ref "C82") (pin "2") (pinfunction "2_2") (pintype "passive"))
      (node (ref "FB2") (pin "P$2") (pinfunction "2_P$2") (pintype "passive"))
      (node (ref "IC10") (pin "8") (pinfunction "V+_8") (pintype "power_in"))
      (node (ref "IC11") (pin "8") (pinfunction "V+_8") (pintype "power_in"))
      (node (ref "IC12") (pin "7") (pinfunction "V+_7") (pintype "power_in"))
      (node (ref "IC15") (pin "2") (pinfunction "VIN_2") (pintype "passive"))
      (node (ref "IC16") (pin "1") (pinfunction "VDD_1") (pintype "power_in"))
      (node (ref "IC17") (pin "5") (pinfunction "VDD_5") (pintype "power_in"))
      (node (ref "IC19") (pin "3") (pinfunction "V+_3") (pintype "power_in"))
      (node (ref "IC20") (pin "1") (pinfunction "+VCC_1") (pintype "passive"))
      (node (ref "R86") (pin "1") (pinfunction "1_1") (pintype "passive"))
      (node (ref "R91") (pin "2") (pinfunction "2_2") (pintype "passive"))
      (node (ref "ZD2") (pin "C") (pinfunction "C_C") (pintype "passive"))
    )
    (net (code "195") (name "V-") (class "Default")
      (node (ref "C54") (pin "2") (pinfunction "2_2") (pintype "passive"))
      (node (ref "C55") (pin "2") (pinfunction "2_2") (pintype "passive"))
      (node (ref "C56") (pin "1") (pinfunction "1_1") (pintype "passive"))
      (node (ref "C57") (pin "2") (pinfunction "2_2") (pintype "passive"))
      (node (ref "C58") (pin "2") (pinfunction "2_2") (pintype "passive"))
      (node (ref "C84") (pin "2") (pinfunction "2_2") (pintype "passive"))
      (node (ref "FB3") (pin "P$2") (pinfunction "2_P$2") (pintype "passive"))
      (node (ref "IC10") (pin "4") (pinfunction "V-_4") (pintype "power_in"))
      (node (ref "IC11") (pin "4") (pinfunction "V-_4") (pintype "power_in"))
      (node (ref "IC12") (pin "4") (pinfunction "V-_4") (pintype "power_in"))
      (node (ref "IC19") (pin "12") (pinfunction "GND_12") (pintype "power_in"))
      (node (ref "R104") (pin "1") (pinfunction "1_1") (pintype "passive"))
    )
    (net (code "196") (name "unconnected-(IC1-PGOOD-Pad7)") (class "Default")
      (node (ref "IC1") (pin "7") (pinfunction "PGOOD_7") (pintype "output"))
    )
    (net (code "197") (name "unconnected-(IC1-PLLIN{slash}MODE-Pad1)") (class "Default")
      (node (ref "IC1") (pin "1") (pinfunction "PLLIN/MODE_1") (pintype "input"))
    )
    (net (code "198") (name "unconnected-(IC3-SD-Pad3)") (class "Default")
      (node (ref "IC3") (pin "3") (pinfunction "SD_3") (pintype "input"))
    )
    (net (code "199") (name "unconnected-(IC3-SENSE-Pad2)") (class "Default")
      (node (ref "IC3") (pin "2") (pinfunction "SENSE_2") (pintype "input"))
    )
    (net (code "200") (name "unconnected-(IC3-VTAP-Pad6)") (class "Default")
      (node (ref "IC3") (pin "6") (pinfunction "VTAP_6") (pintype "input"))
    )
    (net (code "201") (name "unconnected-(IC5-Y3-Pad3)") (class "Default")
      (node (ref "IC5") (pin "3") (pinfunction "Y3_3") (pintype "output"))
    )
    (net (code "202") (name "unconnected-(IC13A-~{Q}-Pad3)") (class "Default")
      (node (ref "IC13") (pin "3") (pinfunction "~{Q}_3") (pintype "output"))
    )
    (net (code "203") (name "unconnected-(IC14-INTB-Pad19)") (class "Default")
      (node (ref "IC14") (pin "19") (pinfunction "INTB_19") (pintype "output"))
    )
    (net (code "204") (name "unconnected-(IC15-TEMP-Pad3)") (class "Default")
      (node (ref "IC15") (pin "3") (pinfunction "TEMP_3") (pintype "input"))
    )
    (net (code "205") (name "~{ADC_DRDY}") (class "Default")
      (node (ref "IC14") (pin "25") (pinfunction "GPA4_25") (pintype "bidirectional"))
      (node (ref "IC18") (pin "14") (pinfunction "~{DRDY}_14") (pintype "output"))
    )
    (net (code "206") (name "~{DP_DRIVE}") (class "Default")
      (node (ref "Q7") (pin "1") (pinfunction "B_1") (pintype "passive"))
      (node (ref "R39") (pin "1") (pinfunction "1_1") (pintype "passive"))
      (node (ref "R79") (pin "1") (pinfunction "1_1") (pintype "passive"))
    )
    (net (code "207") (name "~{OVP_FAULT}") (class "Default")
      (node (ref "IC13") (pin "6") (pinfunction "~{CLR}_6") (pintype "input"))
      (node (ref "LED4") (pin "C") (pinfunction "C_C") (pintype "passive"))
      (node (ref "Q21") (pin "3") (pinfunction "D_3") (pintype "passive"))
      (node (ref "R74") (pin "2") (pinfunction "2_2") (pintype "passive"))
    )
    (net (code "208") (name "~{OVP_LE}") (class "Default")
      (node (ref "IC14") (pin "6") (pinfunction "GPB5_6") (pintype "bidirectional"))
      (node (ref "IC20") (pin "5") (pinfunction "~{LE}_5") (pintype "input"))
    )
    (net (code "209") (name "~{RESET}") (class "Default")
      (node (ref "IC14") (pin "18") (pinfunction "~{RESET}_18") (pintype "input"))
      (node (ref "IC7") (pin "12") (pinfunction "B3_12") (pintype "output"))
    )
    (net (code "210") (name "~{SET_DP}") (class "Default")
      (node (ref "IC14") (pin "1") (pinfunction "GPB0_1") (pintype "bidirectional"))
      (node (ref "Q16") (pin "1") (pinfunction "G_1") (pintype "passive"))
      (node (ref "R76") (pin "2") (pinfunction "2_2") (pintype "passive"))
    )
  )
)
